# axiom_beta_sensor_cmv12000_tht_v0_16_r1_.net
KiCad netlist of a schematic drawn in EAGLE
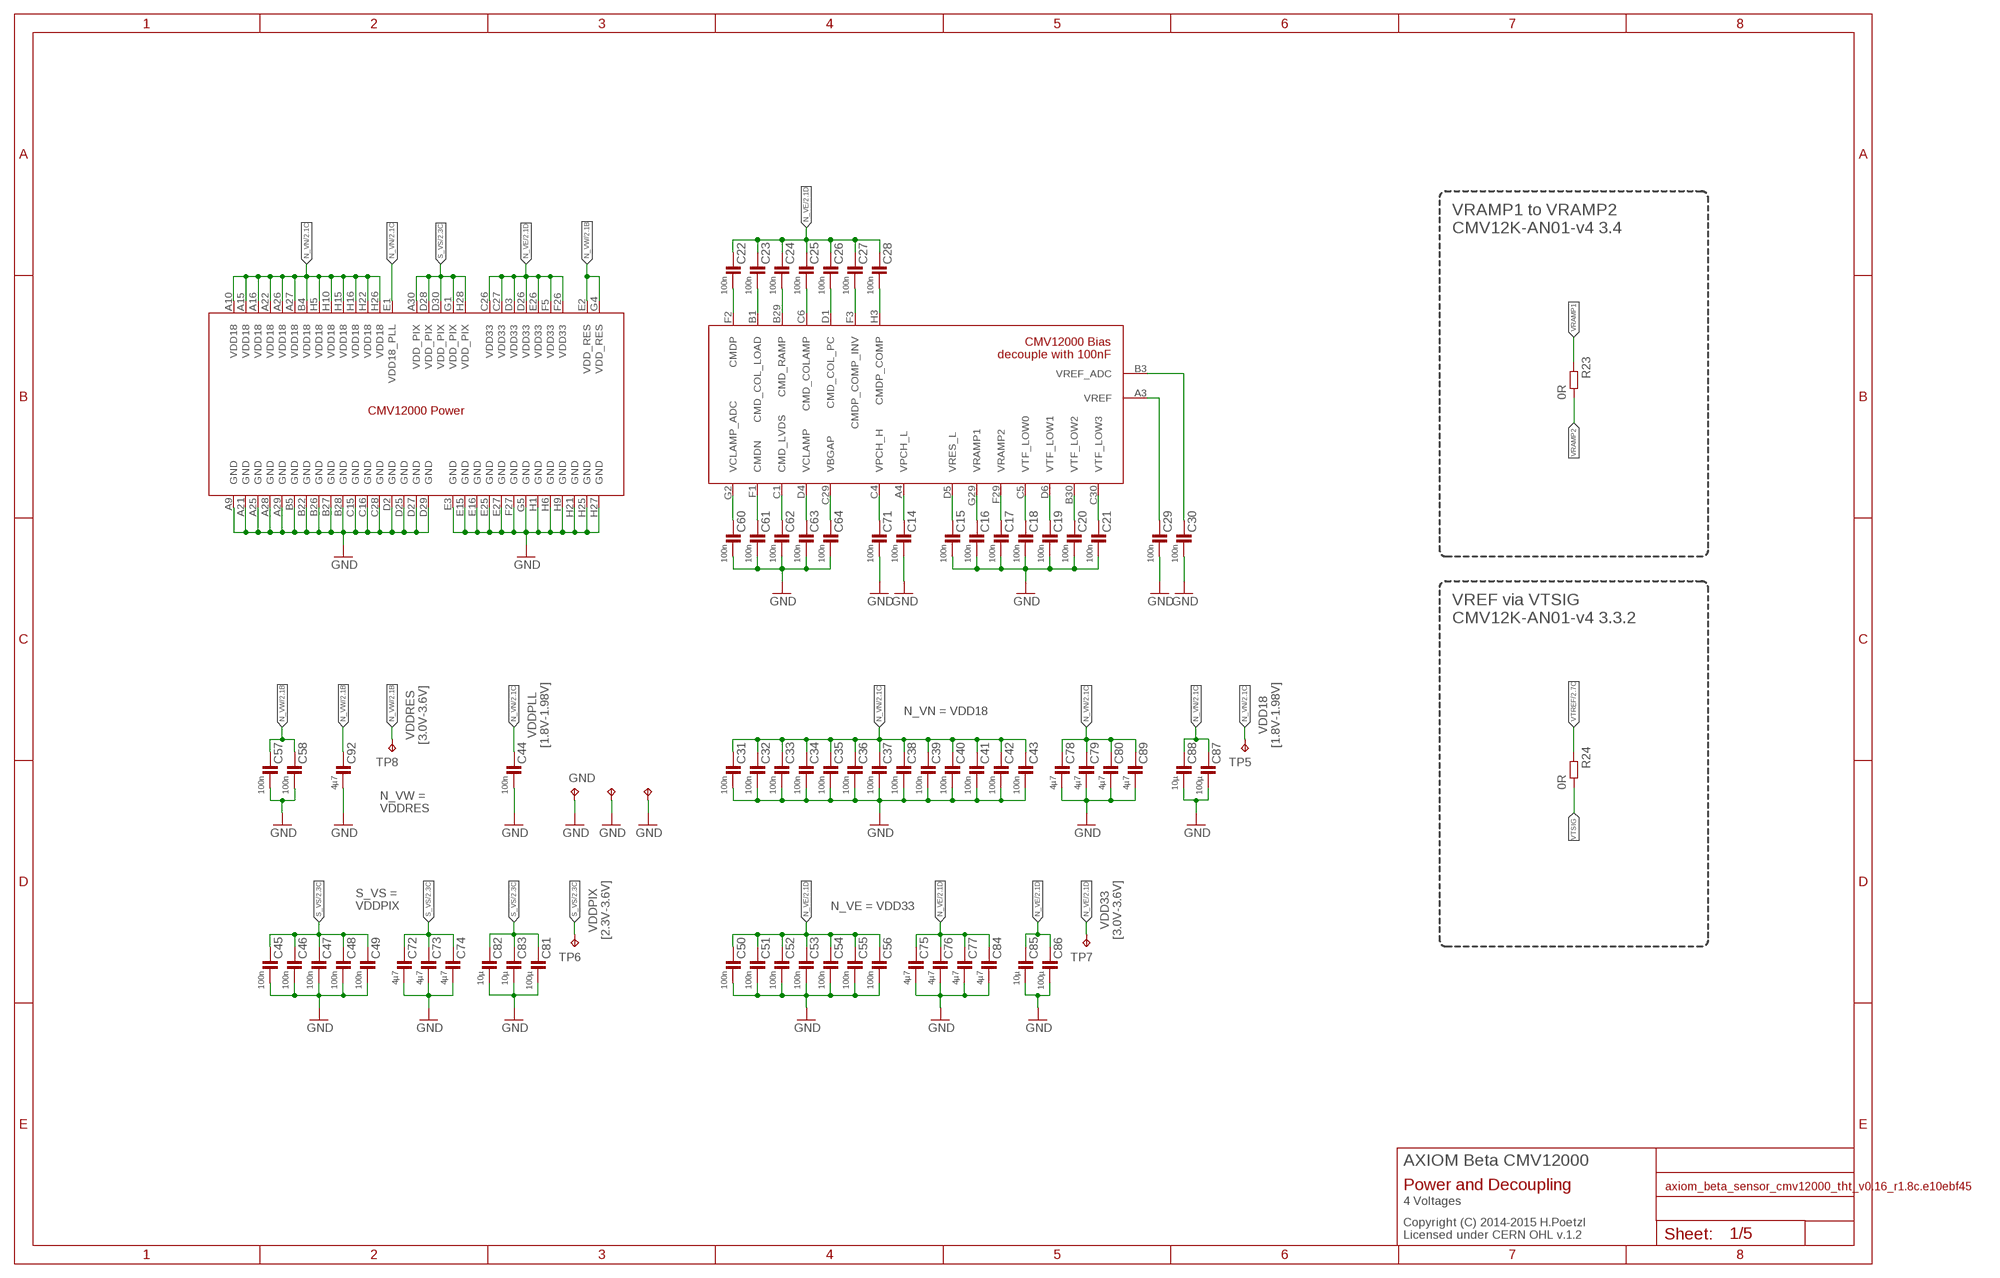
[diagram p0: schematic, sheet 1]
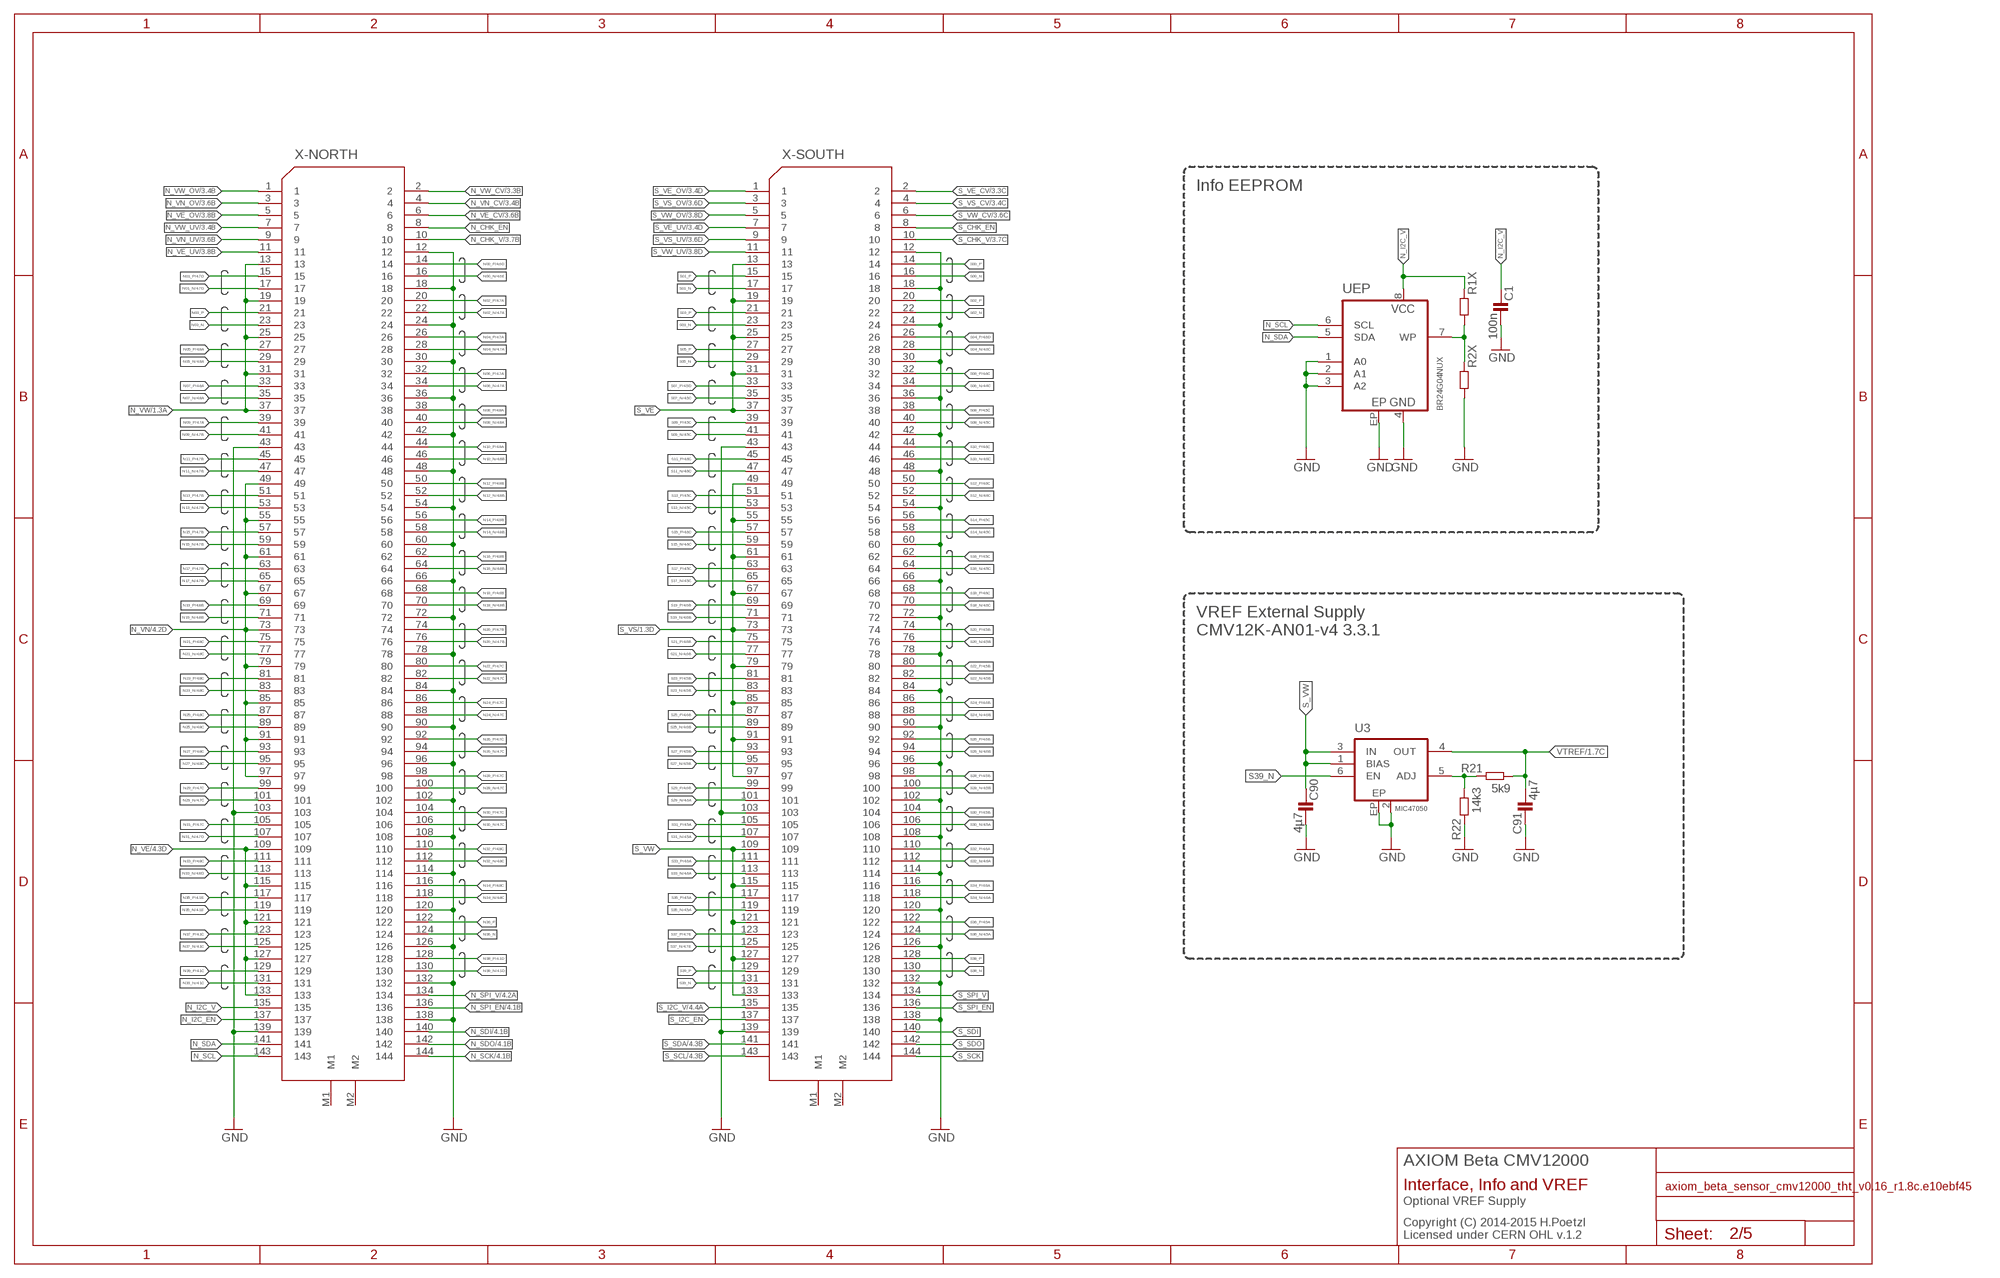
[diagram p1: schematic, sheet 2]
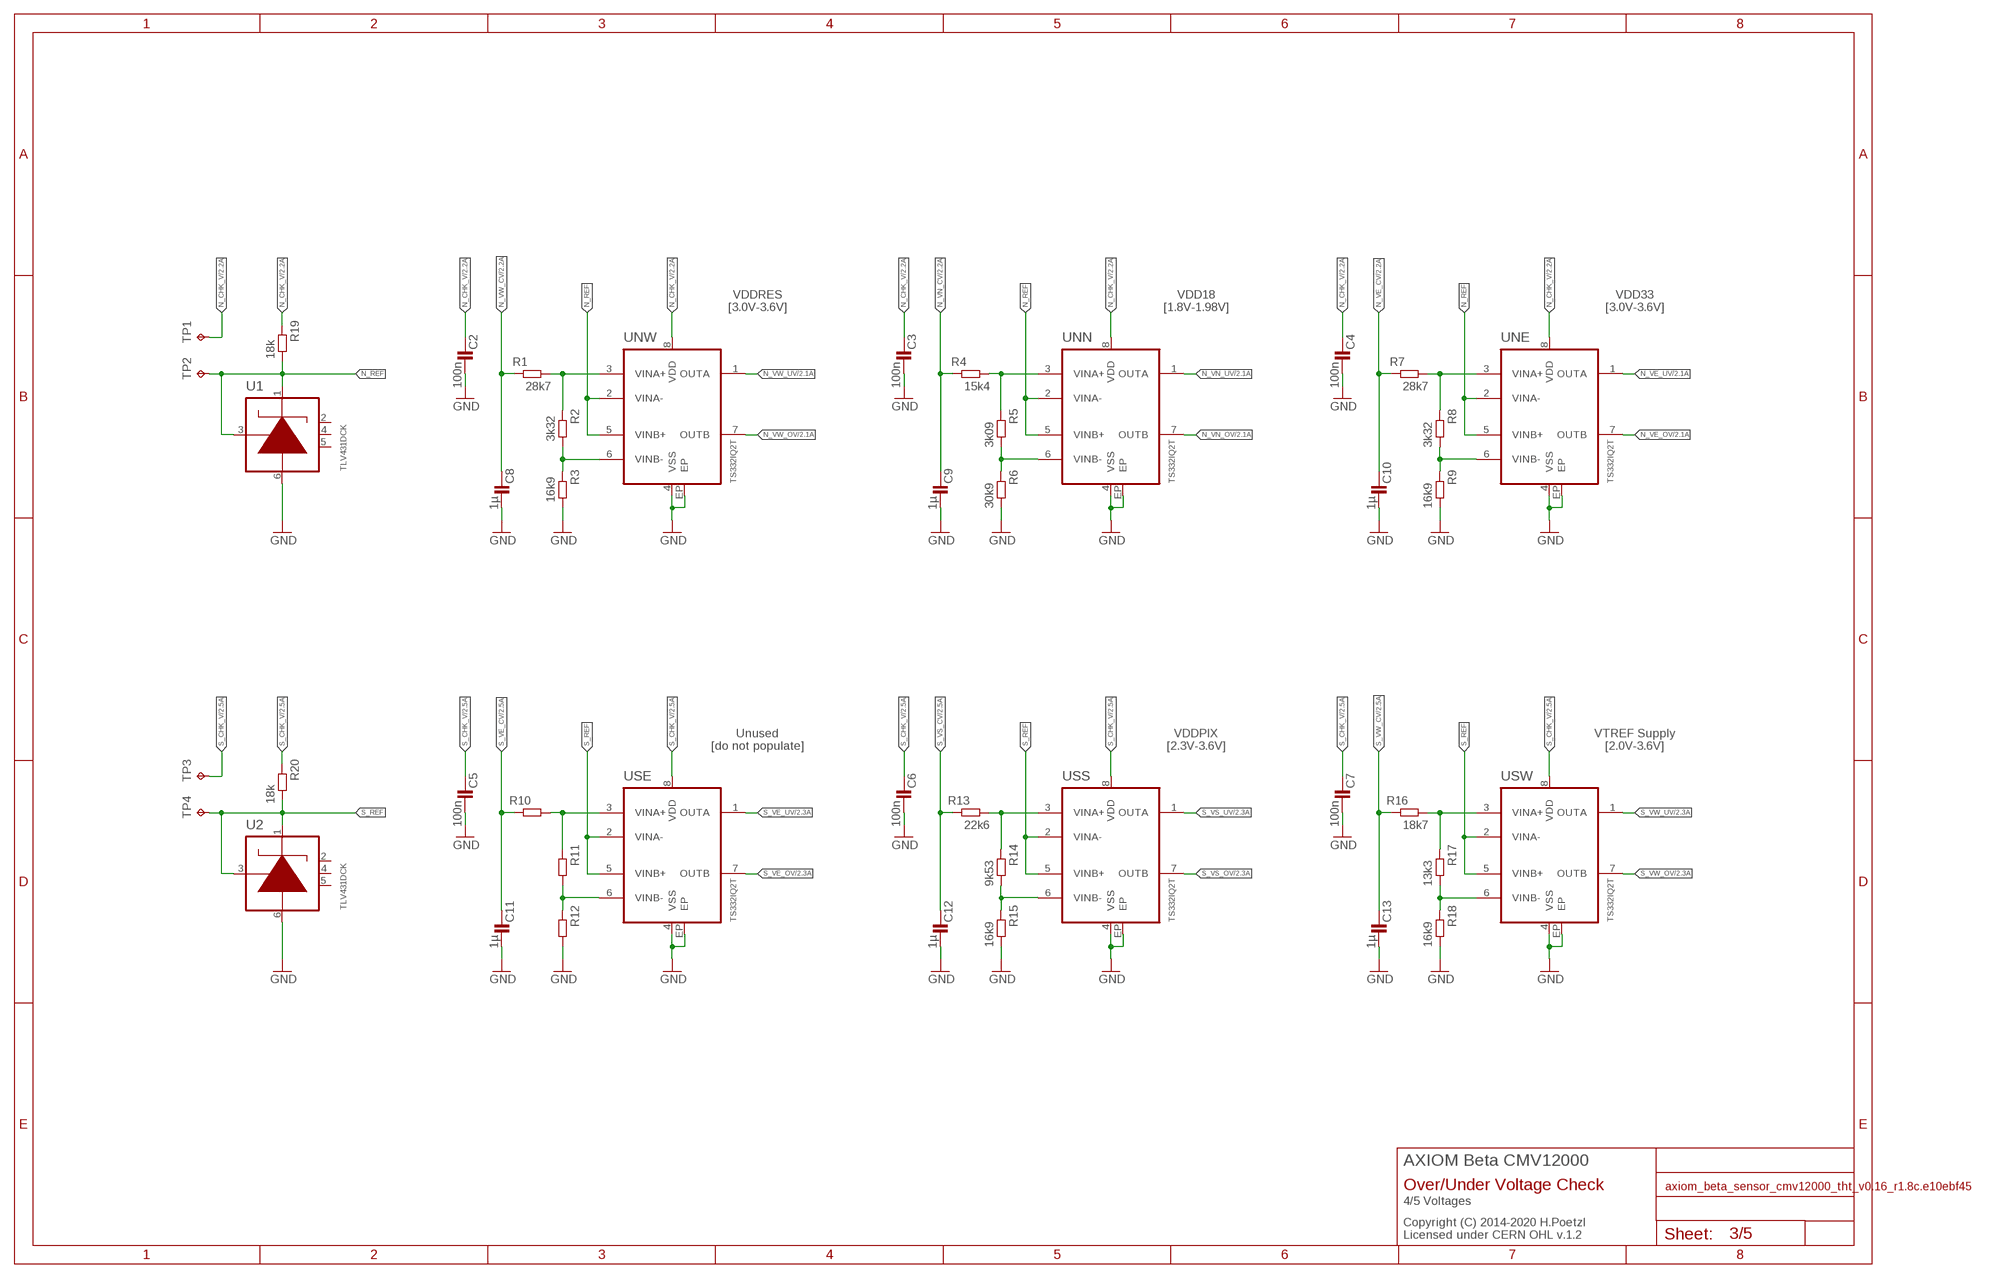
[diagram p2: schematic, sheet 3]
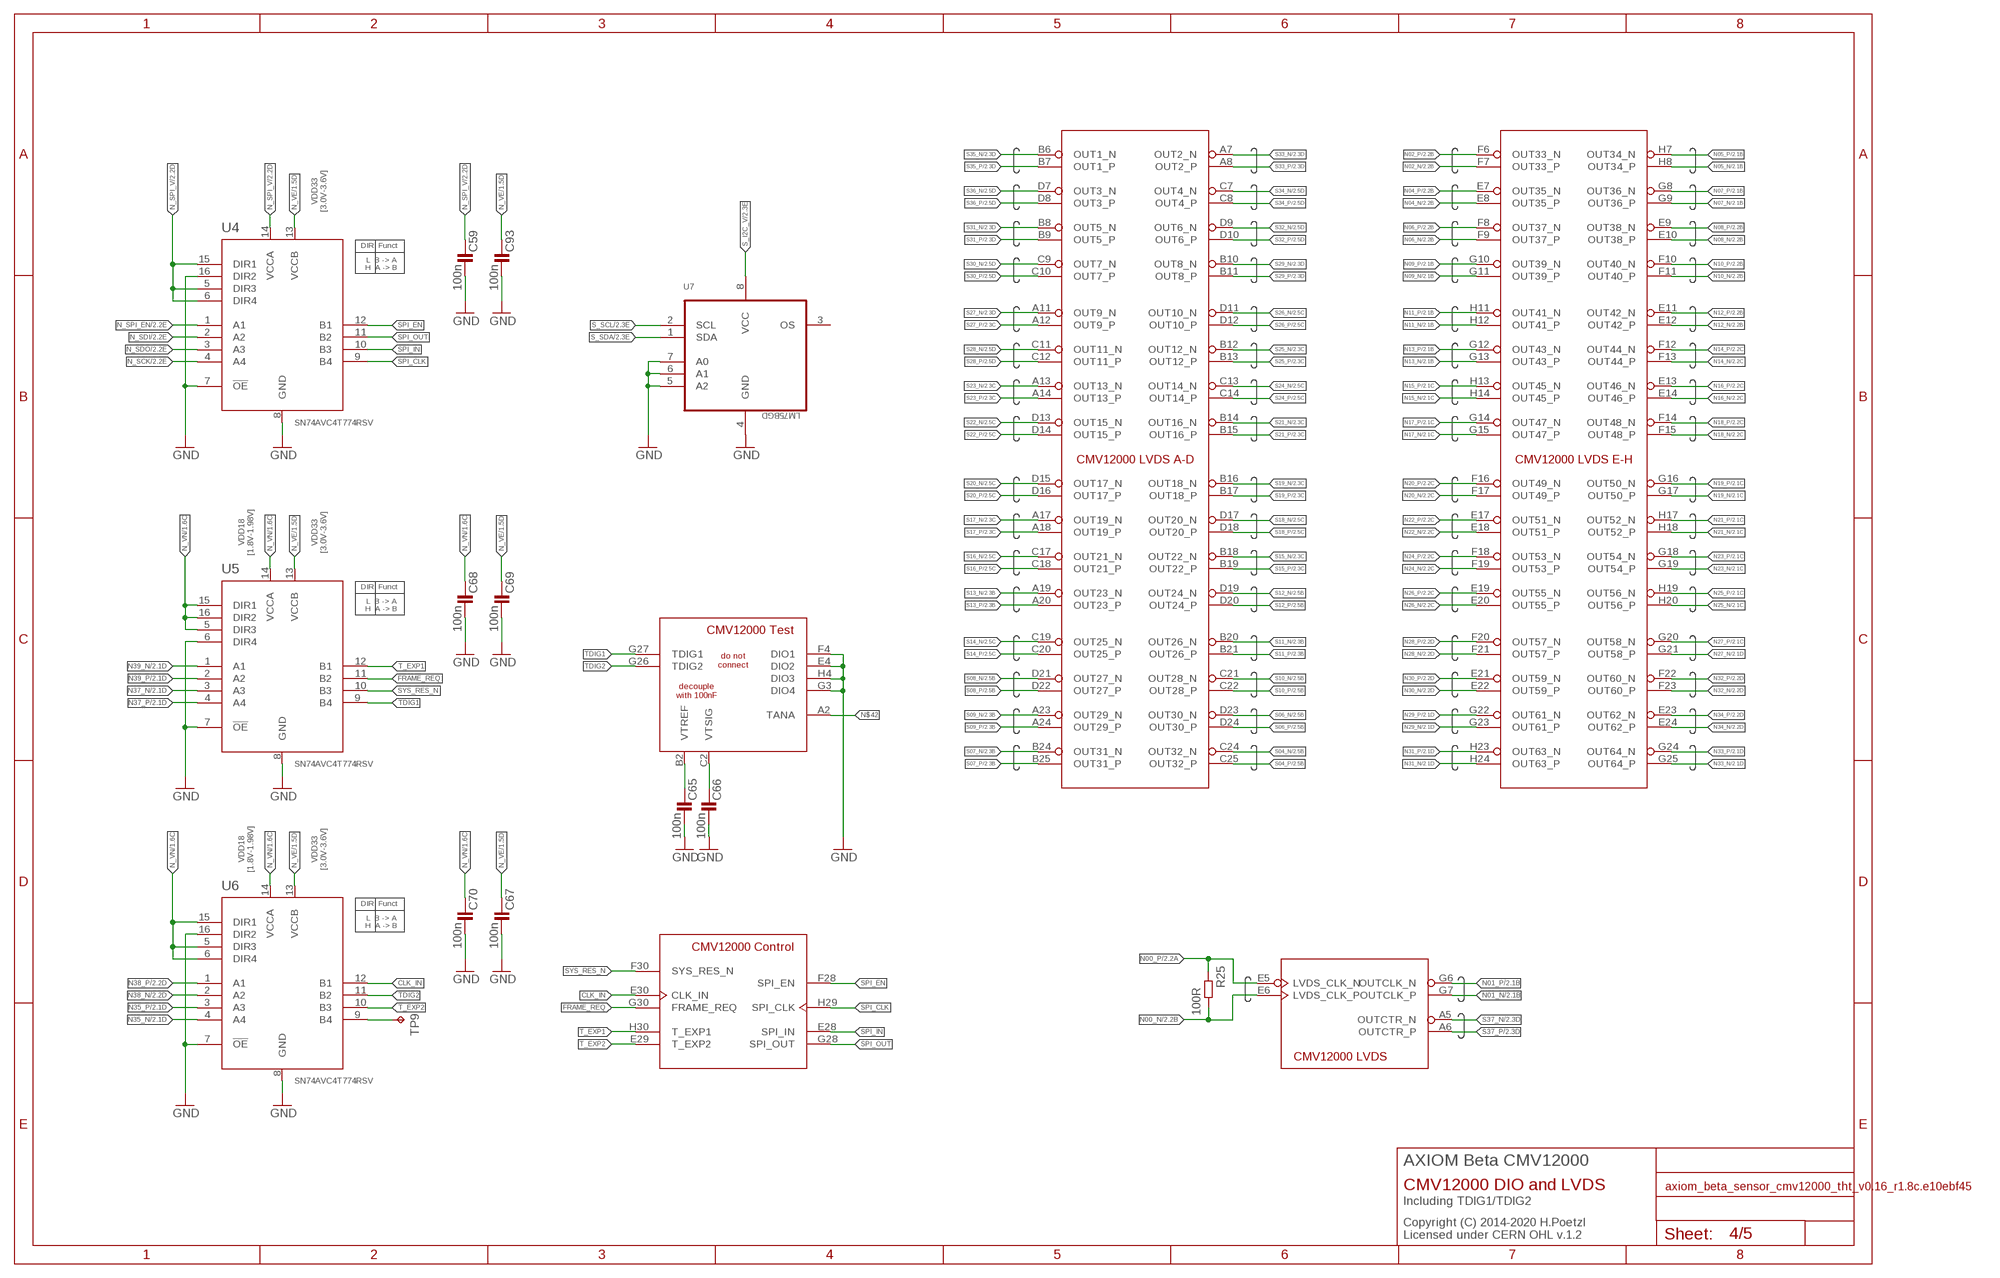
[diagram p3: schematic, sheet 4]
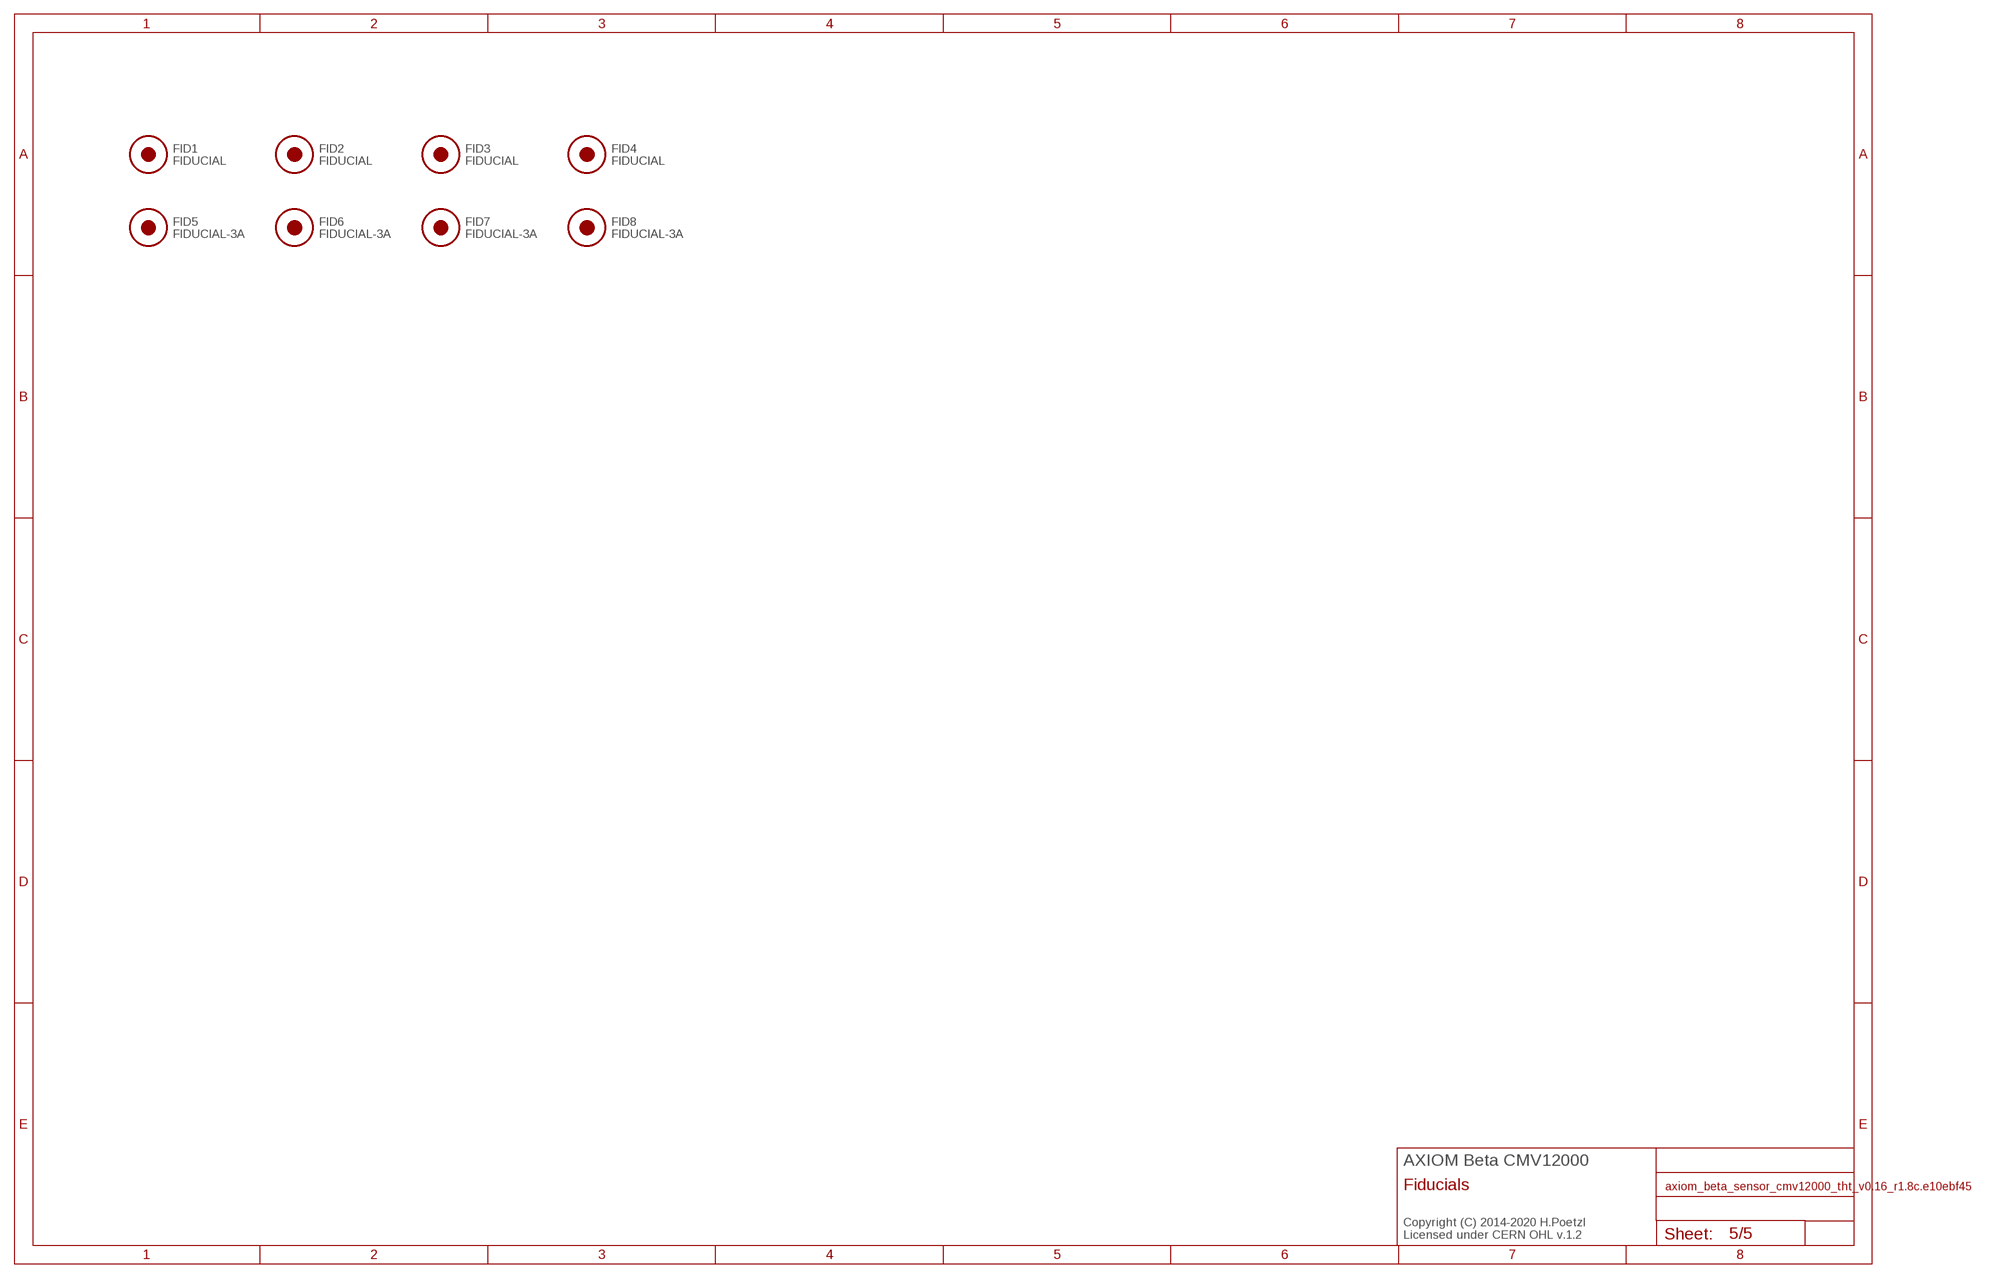
[diagram p4: schematic, sheet 5]

(export (version "E")
  (design (tool "Eeschema 10.0.6"))
  (components
    (comp (ref "C1")
      (value "100n")
      (footprint "eagle-import:0402-C")
      (libsource (lib "eagle-import") (part "C0402-C"))
    )
    (comp (ref "C90")
      (value "4µ7")
      (footprint "eagle-import:0402-C")
      (libsource (lib "eagle-import") (part "C0402-C"))
    )
    (comp (ref "C91")
      (value "4µ7")
      (footprint "eagle-import:0402-C")
      (libsource (lib "eagle-import") (part "C0402-C"))
    )
    (comp (ref "R1X")
      (value "R0402-C")
      (footprint "eagle-import:0402-C")
      (libsource (lib "eagle-import") (part "R0402-C"))
    )
    (comp (ref "R2X")
      (value "R0402-C")
      (footprint "eagle-import:0402-C")
      (libsource (lib "eagle-import") (part "R0402-C"))
    )
    (comp (ref "R21")
      (value "5k9")
      (footprint "eagle-import:0402-C")
      (libsource (lib "eagle-import") (part "R0402-C"))
    )
    (comp (ref "R22")
      (value "14k3")
      (footprint "eagle-import:0402-C")
      (libsource (lib "eagle-import") (part "R0402-C"))
    )
    (comp (ref "U3")
      (value "MIC47050")
      (footprint "eagle-import:MLF-6")
      (libsource (lib "eagle-import") (part "MIC47050-ADJ"))
    )
    (comp (ref "UEP")
      (value "BR24G04NUX")
      (footprint "eagle-import:DFN200X300X100-9N")
      (libsource (lib "eagle-import") (part "BR24G04NUX"))
    )
    (comp (ref "X-NORTH")
      (value "FX10-144P")
      (footprint "eagle-import:FX10A-144P")
      (libsource (lib "eagle-import") (part "FX10-144P"))
    )
    (comp (ref "X-SOUTH")
      (value "FX10-144P")
      (footprint "eagle-import:FX10A-144P")
      (libsource (lib "eagle-import") (part "FX10-144P"))
    )
    (comp (ref "C14")
      (value "100n")
      (footprint "eagle-import:0402-C")
      (libsource (lib "eagle-import") (part "C0402-C"))
    )
    (comp (ref "C15")
      (value "100n")
      (footprint "eagle-import:0402-C")
      (libsource (lib "eagle-import") (part "C0402-C"))
    )
    (comp (ref "C16")
      (value "100n")
      (footprint "eagle-import:0402-C")
      (libsource (lib "eagle-import") (part "C0402-C"))
    )
    (comp (ref "C17")
      (value "100n")
      (footprint "eagle-import:0402-C")
      (libsource (lib "eagle-import") (part "C0402-C"))
    )
    (comp (ref "C18")
      (value "100n")
      (footprint "eagle-import:0402-C")
      (libsource (lib "eagle-import") (part "C0402-C"))
    )
    (comp (ref "C19")
      (value "100n")
      (footprint "eagle-import:0402-C")
      (libsource (lib "eagle-import") (part "C0402-C"))
    )
    (comp (ref "C20")
      (value "100n")
      (footprint "eagle-import:0402-C")
      (libsource (lib "eagle-import") (part "C0402-C"))
    )
    (comp (ref "C21")
      (value "100n")
      (footprint "eagle-import:0402-C")
      (libsource (lib "eagle-import") (part "C0402-C"))
    )
    (comp (ref "C22")
      (value "100n")
      (footprint "eagle-import:0402-C")
      (libsource (lib "eagle-import") (part "C0402-C"))
    )
    (comp (ref "C23")
      (value "100n")
      (footprint "eagle-import:0402-C")
      (libsource (lib "eagle-import") (part "C0402-C"))
    )
    (comp (ref "C24")
      (value "100n")
      (footprint "eagle-import:0402-C")
      (libsource (lib "eagle-import") (part "C0402-C"))
    )
    (comp (ref "C25")
      (value "100n")
      (footprint "eagle-import:0402-C")
      (libsource (lib "eagle-import") (part "C0402-C"))
    )
    (comp (ref "C26")
      (value "100n")
      (footprint "eagle-import:0402-C")
      (libsource (lib "eagle-import") (part "C0402-C"))
    )
    (comp (ref "C27")
      (value "100n")
      (footprint "eagle-import:0402-C")
      (libsource (lib "eagle-import") (part "C0402-C"))
    )
    (comp (ref "C28")
      (value "100n")
      (footprint "eagle-import:0402-C")
      (libsource (lib "eagle-import") (part "C0402-C"))
    )
    (comp (ref "C29")
      (value "100n")
      (footprint "eagle-import:0402-C")
      (libsource (lib "eagle-import") (part "C0402-C"))
    )
    (comp (ref "C30")
      (value "100n")
      (footprint "eagle-import:0402-C")
      (libsource (lib "eagle-import") (part "C0402-C"))
    )
    (comp (ref "C31")
      (value "100n")
      (footprint "eagle-import:0402-C")
      (libsource (lib "eagle-import") (part "C0402-C"))
    )
    (comp (ref "C32")
      (value "100n")
      (footprint "eagle-import:0402-C")
      (libsource (lib "eagle-import") (part "C0402-C"))
    )
    (comp (ref "C33")
      (value "100n")
      (footprint "eagle-import:0402-C")
      (libsource (lib "eagle-import") (part "C0402-C"))
    )
    (comp (ref "C34")
      (value "100n")
      (footprint "eagle-import:0402-C")
      (libsource (lib "eagle-import") (part "C0402-C"))
    )
    (comp (ref "C35")
      (value "100n")
      (footprint "eagle-import:0402-C")
      (libsource (lib "eagle-import") (part "C0402-C"))
    )
    (comp (ref "C36")
      (value "100n")
      (footprint "eagle-import:0402-C")
      (libsource (lib "eagle-import") (part "C0402-C"))
    )
    (comp (ref "C37")
      (value "100n")
      (footprint "eagle-import:0402-C")
      (libsource (lib "eagle-import") (part "C0402-C"))
    )
    (comp (ref "C38")
      (value "100n")
      (footprint "eagle-import:0402-C")
      (libsource (lib "eagle-import") (part "C0402-C"))
    )
    (comp (ref "C39")
      (value "100n")
      (footprint "eagle-import:0402-C")
      (libsource (lib "eagle-import") (part "C0402-C"))
    )
    (comp (ref "C40")
      (value "100n")
      (footprint "eagle-import:0402-C")
      (libsource (lib "eagle-import") (part "C0402-C"))
    )
    (comp (ref "C41")
      (value "100n")
      (footprint "eagle-import:0402-C")
      (libsource (lib "eagle-import") (part "C0402-C"))
    )
    (comp (ref "C42")
      (value "100n")
      (footprint "eagle-import:0402-C")
      (libsource (lib "eagle-import") (part "C0402-C"))
    )
    (comp (ref "C43")
      (value "100n")
      (footprint "eagle-import:0402-C")
      (libsource (lib "eagle-import") (part "C0402-C"))
    )
    (comp (ref "C44")
      (value "100n")
      (footprint "eagle-import:0402-C")
      (libsource (lib "eagle-import") (part "C0402-C"))
    )
    (comp (ref "C45")
      (value "100n")
      (footprint "eagle-import:0402-C")
      (libsource (lib "eagle-import") (part "C0402-C"))
    )
    (comp (ref "C46")
      (value "100n")
      (footprint "eagle-import:0402-C")
      (libsource (lib "eagle-import") (part "C0402-C"))
    )
    (comp (ref "C47")
      (value "100n")
      (footprint "eagle-import:0402-C")
      (libsource (lib "eagle-import") (part "C0402-C"))
    )
    (comp (ref "C48")
      (value "100n")
      (footprint "eagle-import:0402-C")
      (libsource (lib "eagle-import") (part "C0402-C"))
    )
    (comp (ref "C49")
      (value "100n")
      (footprint "eagle-import:0402-C")
      (libsource (lib "eagle-import") (part "C0402-C"))
    )
    (comp (ref "C50")
      (value "100n")
      (footprint "eagle-import:0402-C")
      (libsource (lib "eagle-import") (part "C0402-C"))
    )
    (comp (ref "C51")
      (value "100n")
      (footprint "eagle-import:0402-C")
      (libsource (lib "eagle-import") (part "C0402-C"))
    )
    (comp (ref "C52")
      (value "100n")
      (footprint "eagle-import:0402-C")
      (libsource (lib "eagle-import") (part "C0402-C"))
    )
    (comp (ref "C53")
      (value "100n")
      (footprint "eagle-import:0402-C")
      (libsource (lib "eagle-import") (part "C0402-C"))
    )
    (comp (ref "C54")
      (value "100n")
      (footprint "eagle-import:0402-C")
      (libsource (lib "eagle-import") (part "C0402-C"))
    )
    (comp (ref "C55")
      (value "100n")
      (footprint "eagle-import:0402-C")
      (libsource (lib "eagle-import") (part "C0402-C"))
    )
    (comp (ref "C56")
      (value "100n")
      (footprint "eagle-import:0402-C")
      (libsource (lib "eagle-import") (part "C0402-C"))
    )
    (comp (ref "C57")
      (value "100n")
      (footprint "eagle-import:0402-C")
      (libsource (lib "eagle-import") (part "C0402-C"))
    )
    (comp (ref "C58")
      (value "100n")
      (footprint "eagle-import:0402-C")
      (libsource (lib "eagle-import") (part "C0402-C"))
    )
    (comp (ref "C60")
      (value "100n")
      (footprint "eagle-import:0402-C")
      (libsource (lib "eagle-import") (part "C0402-C"))
    )
    (comp (ref "C61")
      (value "100n")
      (footprint "eagle-import:0402-C")
      (libsource (lib "eagle-import") (part "C0402-C"))
    )
    (comp (ref "C62")
      (value "100n")
      (footprint "eagle-import:0402-C")
      (libsource (lib "eagle-import") (part "C0402-C"))
    )
    (comp (ref "C63")
      (value "100n")
      (footprint "eagle-import:0402-C")
      (libsource (lib "eagle-import") (part "C0402-C"))
    )
    (comp (ref "C64")
      (value "100n")
      (footprint "eagle-import:0402-C")
      (libsource (lib "eagle-import") (part "C0402-C"))
    )
    (comp (ref "C71")
      (value "100n")
      (footprint "eagle-import:0402-C")
      (libsource (lib "eagle-import") (part "C0402-C"))
    )
    (comp (ref "C72")
      (value "4µ7")
      (footprint "eagle-import:0402-B")
      (libsource (lib "eagle-import") (part "C0402-B"))
    )
    (comp (ref "C73")
      (value "4µ7")
      (footprint "eagle-import:0402-C")
      (libsource (lib "eagle-import") (part "C0402-C"))
    )
    (comp (ref "C74")
      (value "4µ7")
      (footprint "eagle-import:0402-C")
      (libsource (lib "eagle-import") (part "C0402-C"))
    )
    (comp (ref "C75")
      (value "4µ7")
      (footprint "eagle-import:0402-C")
      (libsource (lib "eagle-import") (part "C0402-C"))
    )
    (comp (ref "C76")
      (value "4µ7")
      (footprint "eagle-import:0402-C")
      (libsource (lib "eagle-import") (part "C0402-C"))
    )
    (comp (ref "C77")
      (value "4µ7")
      (footprint "eagle-import:0402-B")
      (libsource (lib "eagle-import") (part "C0402-B"))
    )
    (comp (ref "C78")
      (value "4µ7")
      (footprint "eagle-import:0402-B")
      (libsource (lib "eagle-import") (part "C0402-B"))
    )
    (comp (ref "C79")
      (value "4µ7")
      (footprint "eagle-import:0402-C")
      (libsource (lib "eagle-import") (part "C0402-C"))
    )
    (comp (ref "C80")
      (value "4µ7")
      (footprint "eagle-import:0402-C")
      (libsource (lib "eagle-import") (part "C0402-C"))
    )
    (comp (ref "C81")
      (value "100µ")
      (footprint "eagle-import:1206-B")
      (libsource (lib "eagle-import") (part "C1206-B"))
    )
    (comp (ref "C82")
      (value "10µ")
      (footprint "eagle-import:0603-C")
      (libsource (lib "eagle-import") (part "C0603-C"))
    )
    (comp (ref "C83")
      (value "10µ")
      (footprint "eagle-import:0603-C")
      (libsource (lib "eagle-import") (part "C0603-C"))
    )
    (comp (ref "C84")
      (value "4µ7")
      (footprint "eagle-import:0402-C")
      (libsource (lib "eagle-import") (part "C0402-C"))
    )
    (comp (ref "C85")
      (value "10µ")
      (footprint "eagle-import:0603-C")
      (libsource (lib "eagle-import") (part "C0603-C"))
    )
    (comp (ref "C86")
      (value "100µ")
      (footprint "eagle-import:1206-B")
      (libsource (lib "eagle-import") (part "C1206-B"))
    )
    (comp (ref "C87")
      (value "100µ")
      (footprint "eagle-import:1206-B")
      (libsource (lib "eagle-import") (part "C1206-B"))
    )
    (comp (ref "C88")
      (value "10µ")
      (footprint "eagle-import:0603-C")
      (libsource (lib "eagle-import") (part "C0603-C"))
    )
    (comp (ref "C89")
      (value "4µ7")
      (footprint "eagle-import:0402-C")
      (libsource (lib "eagle-import") (part "C0402-C"))
    )
    (comp (ref "C92")
      (value "4µ7")
      (footprint "eagle-import:0402-C")
      (libsource (lib "eagle-import") (part "C0402-C"))
    )
    (comp (ref "GND")
      (value "TPTP10R")
      (footprint "eagle-import:TP10R")
      (libsource (lib "eagle-import") (part "TPTP10R"))
    )
    (comp (ref "GND75")
      (value "TPTP10R")
      (footprint "eagle-import:TP10R")
      (libsource (lib "eagle-import") (part "TPTP10R"))
    )
    (comp (ref "GND77")
      (value "TPTP10R")
      (footprint "eagle-import:TP10R")
      (libsource (lib "eagle-import") (part "TPTP10R"))
    )
    (comp (ref "R23")
      (value "0R")
      (footprint "eagle-import:0402-C")
      (libsource (lib "eagle-import") (part "R0402-C"))
    )
    (comp (ref "R24")
      (value "0R")
      (footprint "eagle-import:0402-C")
      (libsource (lib "eagle-import") (part "R0402-C"))
    )
    (comp (ref "SENSOR")
      (value "CMV12000ANDON")
      (footprint "eagle-import:10-30-07-237-400T4")
      (libsource (lib "eagle-import") (part "CMV12000ANDON"))
    )
    (comp (ref "TP5")
      (value "TPTP10R")
      (footprint "eagle-import:TP10R")
      (libsource (lib "eagle-import") (part "TPTP10R"))
    )
    (comp (ref "TP6")
      (value "TPTP10R")
      (footprint "eagle-import:TP10R")
      (libsource (lib "eagle-import") (part "TPTP10R"))
    )
    (comp (ref "TP7")
      (value "TPTP10R")
      (footprint "eagle-import:TP10R")
      (libsource (lib "eagle-import") (part "TPTP10R"))
    )
    (comp (ref "TP8")
      (value "TPTP10R")
      (footprint "eagle-import:TP10R")
      (libsource (lib "eagle-import") (part "TPTP10R"))
    )
    (comp (ref "FID1")
      (value "FIDUCIAL")
      (footprint "eagle-import:FID_ARROW")
      (libsource (lib "eagle-import") (part "FIDUCIAL"))
    )
    (comp (ref "FID2")
      (value "FIDUCIAL")
      (footprint "eagle-import:FID_ARROW")
      (libsource (lib "eagle-import") (part "FIDUCIAL"))
    )
    (comp (ref "FID3")
      (value "FIDUCIAL")
      (footprint "eagle-import:FID_ARROW")
      (libsource (lib "eagle-import") (part "FIDUCIAL"))
    )
    (comp (ref "FID4")
      (value "FIDUCIAL")
      (footprint "eagle-import:FID_ARROW")
      (libsource (lib "eagle-import") (part "FIDUCIAL"))
    )
    (comp (ref "FID5")
      (value "FIDUCIAL-3A")
      (footprint "eagle-import:FID_3ARROW")
      (libsource (lib "eagle-import") (part "FIDUCIAL-3A"))
    )
    (comp (ref "FID6")
      (value "FIDUCIAL-3A")
      (footprint "eagle-import:FID_3ARROW")
      (libsource (lib "eagle-import") (part "FIDUCIAL-3A"))
    )
    (comp (ref "FID7")
      (value "FIDUCIAL-3A")
      (footprint "eagle-import:FID_3ARROW")
      (libsource (lib "eagle-import") (part "FIDUCIAL-3A"))
    )
    (comp (ref "FID8")
      (value "FIDUCIAL-3A")
      (footprint "eagle-import:FID_3ARROW")
      (libsource (lib "eagle-import") (part "FIDUCIAL-3A"))
    )
    (comp (ref "C59")
      (value "100n")
      (footprint "eagle-import:0402-C")
      (libsource (lib "eagle-import") (part "C0402-C"))
    )
    (comp (ref "C65")
      (value "100n")
      (footprint "eagle-import:0402-C")
      (libsource (lib "eagle-import") (part "C0402-C"))
    )
    (comp (ref "C66")
      (value "100n")
      (footprint "eagle-import:0402-C")
      (libsource (lib "eagle-import") (part "C0402-C"))
    )
    (comp (ref "C67")
      (value "100n")
      (footprint "eagle-import:0402-C")
      (libsource (lib "eagle-import") (part "C0402-C"))
    )
    (comp (ref "C68")
      (value "100n")
      (footprint "eagle-import:0402-C")
      (libsource (lib "eagle-import") (part "C0402-C"))
    )
    (comp (ref "C69")
      (value "100n")
      (footprint "eagle-import:0402-C")
      (libsource (lib "eagle-import") (part "C0402-C"))
    )
    (comp (ref "C70")
      (value "100n")
      (footprint "eagle-import:0402-C")
      (libsource (lib "eagle-import") (part "C0402-C"))
    )
    (comp (ref "C93")
      (value "100n")
      (footprint "eagle-import:0402-C")
      (libsource (lib "eagle-import") (part "C0402-C"))
    )
    (comp (ref "R25")
      (value "100R")
      (footprint "eagle-import:0402-C")
      (libsource (lib "eagle-import") (part "R0402-C"))
    )
    (comp (ref "TP9")
      (value "TPTP10R")
      (footprint "eagle-import:TP10R")
      (libsource (lib "eagle-import") (part "TPTP10R"))
    )
    (comp (ref "U4")
      (value "SN74AVC4T774RSV")
      (footprint "eagle-import:QFN40P185X265X55-16N")
      (libsource (lib "eagle-import") (part "SN74AVC4T774RSV"))
    )
    (comp (ref "U5")
      (value "SN74AVC4T774RSV")
      (footprint "eagle-import:QFN40P185X265X55-16N")
      (libsource (lib "eagle-import") (part "SN74AVC4T774RSV"))
    )
    (comp (ref "U6")
      (value "SN74AVC4T774RSV")
      (footprint "eagle-import:QFN40P185X265X55-16N")
      (libsource (lib "eagle-import") (part "SN74AVC4T774RSV"))
    )
    (comp (ref "U7")
      (value "LM75BGD")
      (footprint "eagle-import:SOT996-2_3")
      (libsource (lib "eagle-import") (part "LM75BGD"))
    )
    (comp (ref "C2")
      (value "100n")
      (footprint "eagle-import:0402-C")
      (libsource (lib "eagle-import") (part "C0402-C"))
    )
    (comp (ref "C3")
      (value "100n")
      (footprint "eagle-import:0402-C")
      (libsource (lib "eagle-import") (part "C0402-C"))
    )
    (comp (ref "C4")
      (value "100n")
      (footprint "eagle-import:0402-C")
      (libsource (lib "eagle-import") (part "C0402-C"))
    )
    (comp (ref "C5")
      (value "100n")
      (footprint "eagle-import:0402-C")
      (libsource (lib "eagle-import") (part "C0402-C"))
    )
    (comp (ref "C6")
      (value "100n")
      (footprint "eagle-import:0402-C")
      (libsource (lib "eagle-import") (part "C0402-C"))
    )
    (comp (ref "C7")
      (value "100n")
      (footprint "eagle-import:0402-C")
      (libsource (lib "eagle-import") (part "C0402-C"))
    )
    (comp (ref "C8")
      (value "1µ")
      (footprint "eagle-import:0402-C")
      (libsource (lib "eagle-import") (part "C0402-C"))
    )
    (comp (ref "C9")
      (value "1µ")
      (footprint "eagle-import:0402-C")
      (libsource (lib "eagle-import") (part "C0402-C"))
    )
    (comp (ref "C10")
      (value "1µ")
      (footprint "eagle-import:0402-C")
      (libsource (lib "eagle-import") (part "C0402-C"))
    )
    (comp (ref "C11")
      (value "1µ")
      (footprint "eagle-import:0402-C")
      (libsource (lib "eagle-import") (part "C0402-C"))
    )
    (comp (ref "C12")
      (value "1µ")
      (footprint "eagle-import:0402-C")
      (libsource (lib "eagle-import") (part "C0402-C"))
    )
    (comp (ref "C13")
      (value "1µ")
      (footprint "eagle-import:0402-C")
      (libsource (lib "eagle-import") (part "C0402-C"))
    )
    (comp (ref "R1")
      (value "28k7")
      (footprint "eagle-import:0402-C")
      (libsource (lib "eagle-import") (part "R0402-C"))
    )
    (comp (ref "R2")
      (value "3k32")
      (footprint "eagle-import:0402-C")
      (libsource (lib "eagle-import") (part "R0402-C"))
    )
    (comp (ref "R3")
      (value "16k9")
      (footprint "eagle-import:0402-C")
      (libsource (lib "eagle-import") (part "R0402-C"))
    )
    (comp (ref "R4")
      (value "15k4")
      (footprint "eagle-import:0402-C")
      (libsource (lib "eagle-import") (part "R0402-C"))
    )
    (comp (ref "R5")
      (value "3k09")
      (footprint "eagle-import:0402-C")
      (libsource (lib "eagle-import") (part "R0402-C"))
    )
    (comp (ref "R6")
      (value "30k9")
      (footprint "eagle-import:0402-C")
      (libsource (lib "eagle-import") (part "R0402-C"))
    )
    (comp (ref "R7")
      (value "28k7")
      (footprint "eagle-import:0402-C")
      (libsource (lib "eagle-import") (part "R0402-C"))
    )
    (comp (ref "R8")
      (value "3k32")
      (footprint "eagle-import:0402-C")
      (libsource (lib "eagle-import") (part "R0402-C"))
    )
    (comp (ref "R9")
      (value "16k9")
      (footprint "eagle-import:0402-C")
      (libsource (lib "eagle-import") (part "R0402-C"))
    )
    (comp (ref "R10")
      (value "R0402-C")
      (footprint "eagle-import:0402-C")
      (libsource (lib "eagle-import") (part "R0402-C"))
    )
    (comp (ref "R11")
      (value "R0402-C")
      (footprint "eagle-import:0402-C")
      (libsource (lib "eagle-import") (part "R0402-C"))
    )
    (comp (ref "R12")
      (value "R0402-C")
      (footprint "eagle-import:0402-C")
      (libsource (lib "eagle-import") (part "R0402-C"))
    )
    (comp (ref "R13")
      (value "22k6")
      (footprint "eagle-import:0402-C")
      (libsource (lib "eagle-import") (part "R0402-C"))
    )
    (comp (ref "R14")
      (value "9k53")
      (footprint "eagle-import:0402-C")
      (libsource (lib "eagle-import") (part "R0402-C"))
    )
    (comp (ref "R15")
      (value "16k9")
      (footprint "eagle-import:0402-C")
      (libsource (lib "eagle-import") (part "R0402-C"))
    )
    (comp (ref "R16")
      (value "18k7")
      (footprint "eagle-import:0402-C")
      (libsource (lib "eagle-import") (part "R0402-C"))
    )
    (comp (ref "R17")
      (value "13k3")
      (footprint "eagle-import:0402-C")
      (libsource (lib "eagle-import") (part "R0402-C"))
    )
    (comp (ref "R18")
      (value "16k9")
      (footprint "eagle-import:0402-C")
      (libsource (lib "eagle-import") (part "R0402-C"))
    )
    (comp (ref "R19")
      (value "18k")
      (footprint "eagle-import:0402-C")
      (libsource (lib "eagle-import") (part "R0402-C"))
    )
    (comp (ref "R20")
      (value "18k")
      (footprint "eagle-import:0402-C")
      (libsource (lib "eagle-import") (part "R0402-C"))
    )
    (comp (ref "TP1")
      (value "TPTP10R")
      (footprint "eagle-import:TP10R")
      (libsource (lib "eagle-import") (part "TPTP10R"))
    )
    (comp (ref "TP2")
      (value "TPTP10R")
      (footprint "eagle-import:TP10R")
      (libsource (lib "eagle-import") (part "TPTP10R"))
    )
    (comp (ref "TP3")
      (value "TPTP10R")
      (footprint "eagle-import:TP10R")
      (libsource (lib "eagle-import") (part "TPTP10R"))
    )
    (comp (ref "TP4")
      (value "TPTP10R")
      (footprint "eagle-import:TP10R")
      (libsource (lib "eagle-import") (part "TPTP10R"))
    )
    (comp (ref "U1")
      (value "TLV431DCK")
      (footprint "eagle-import:SOT65P210X110-6N")
      (libsource (lib "eagle-import") (part "TLV431DCK"))
    )
    (comp (ref "U2")
      (value "TLV431DCK")
      (footprint "eagle-import:SOT65P210X110-6N")
      (libsource (lib "eagle-import") (part "TLV431DCK"))
    )
    (comp (ref "UNE")
      (value "TS332IQ2T")
      (footprint "eagle-import:DFN200X200X100-9N")
      (libsource (lib "eagle-import") (part "TS332IQ2T"))
    )
    (comp (ref "UNN")
      (value "TS332IQ2T")
      (footprint "eagle-import:DFN200X200X100-9N")
      (libsource (lib "eagle-import") (part "TS332IQ2T"))
    )
    (comp (ref "UNW")
      (value "TS332IQ2T")
      (footprint "eagle-import:DFN200X200X100-9N")
      (libsource (lib "eagle-import") (part "TS332IQ2T"))
    )
    (comp (ref "USE")
      (value "TS332IQ2T")
      (footprint "eagle-import:DFN200X200X100-9N")
      (libsource (lib "eagle-import") (part "TS332IQ2T"))
    )
    (comp (ref "USS")
      (value "TS332IQ2T")
      (footprint "eagle-import:DFN200X200X100-9N")
      (libsource (lib "eagle-import") (part "TS332IQ2T"))
    )
    (comp (ref "USW")
      (value "TS332IQ2T")
      (footprint "eagle-import:DFN200X200X100-9N")
      (libsource (lib "eagle-import") (part "TS332IQ2T"))
    )
  )
  (nets
    (net (code "1") (name "CLK_IN") (class "Default")
      (node (ref "SENSOR") (pin "E30") (pinfunction "CLK_IN_E30") (pintype "input"))
      (node (ref "U6") (pin "12") (pinfunction "B1_12") (pintype "bidirectional"))
    )
    (net (code "2") (name "FRAME_REQ") (class "Default")
      (node (ref "SENSOR") (pin "G30") (pinfunction "FRAME_REQ_G30") (pintype "input"))
      (node (ref "U5") (pin "11") (pinfunction "B2_11") (pintype "bidirectional"))
    )
    (net (code "3") (name "GND") (class "Default")
      (node (ref "C1") (pin "2") (pinfunction "2_2") (pintype "passive"))
      (node (ref "C10") (pin "2") (pinfunction "2_2") (pintype "passive"))
      (node (ref "C11") (pin "2") (pinfunction "2_2") (pintype "passive"))
      (node (ref "C12") (pin "2") (pinfunction "2_2") (pintype "passive"))
      (node (ref "C13") (pin "2") (pinfunction "2_2") (pintype "passive"))
      (node (ref "C14") (pin "2") (pinfunction "2_2") (pintype "passive"))
      (node (ref "C15") (pin "2") (pinfunction "2_2") (pintype "passive"))
      (node (ref "C16") (pin "2") (pinfunction "2_2") (pintype "passive"))
      (node (ref "C17") (pin "2") (pinfunction "2_2") (pintype "passive"))
      (node (ref "C18") (pin "2") (pinfunction "2_2") (pintype "passive"))
      (node (ref "C19") (pin "2") (pinfunction "2_2") (pintype "passive"))
      (node (ref "C2") (pin "2") (pinfunction "2_2") (pintype "passive"))
      (node (ref "C20") (pin "2") (pinfunction "2_2") (pintype "passive"))
      (node (ref "C21") (pin "2") (pinfunction "2_2") (pintype "passive"))
      (node (ref "C29") (pin "2") (pinfunction "2_2") (pintype "passive"))
      (node (ref "C3") (pin "2") (pinfunction "2_2") (pintype "passive"))
      (node (ref "C30") (pin "2") (pinfunction "2_2") (pintype "passive"))
      (node (ref "C31") (pin "2") (pinfunction "2_2") (pintype "passive"))
      (node (ref "C32") (pin "2") (pinfunction "2_2") (pintype "passive"))
      (node (ref "C33") (pin "2") (pinfunction "2_2") (pintype "passive"))
      (node (ref "C34") (pin "2") (pinfunction "2_2") (pintype "passive"))
      (node (ref "C35") (pin "2") (pinfunction "2_2") (pintype "passive"))
      (node (ref "C36") (pin "2") (pinfunction "2_2") (pintype "passive"))
      (node (ref "C37") (pin "2") (pinfunction "2_2") (pintype "passive"))
      (node (ref "C38") (pin "2") (pinfunction "2_2") (pintype "passive"))
      (node (ref "C39") (pin "2") (pinfunction "2_2") (pintype "passive"))
      (node (ref "C4") (pin "2") (pinfunction "2_2") (pintype "passive"))
      (node (ref "C40") (pin "2") (pinfunction "2_2") (pintype "passive"))
      (node (ref "C41") (pin "2") (pinfunction "2_2") (pintype "passive"))
      (node (ref "C42") (pin "2") (pinfunction "2_2") (pintype "passive"))
      (node (ref "C43") (pin "2") (pinfunction "2_2") (pintype "passive"))
      (node (ref "C44") (pin "2") (pinfunction "2_2") (pintype "passive"))
      (node (ref "C45") (pin "2") (pinfunction "2_2") (pintype "passive"))
      (node (ref "C46") (pin "2") (pinfunction "2_2") (pintype "passive"))
      (node (ref "C47") (pin "2") (pinfunction "2_2") (pintype "passive"))
      (node (ref "C48") (pin "2") (pinfunction "2_2") (pintype "passive"))
      (node (ref "C49") (pin "2") (pinfunction "2_2") (pintype "passive"))
      (node (ref "C5") (pin "2") (pinfunction "2_2") (pintype "passive"))
      (node (ref "C50") (pin "2") (pinfunction "2_2") (pintype "passive"))
      (node (ref "C51") (pin "2") (pinfunction "2_2") (pintype "passive"))
      (node (ref "C52") (pin "2") (pinfunction "2_2") (pintype "passive"))
      (node (ref "C53") (pin "2") (pinfunction "2_2") (pintype "passive"))
      (node (ref "C54") (pin "2") (pinfunction "2_2") (pintype "passive"))
      (node (ref "C55") (pin "2") (pinfunction "2_2") (pintype "passive"))
      (node (ref "C56") (pin "2") (pinfunction "2_2") (pintype "passive"))
      (node (ref "C57") (pin "2") (pinfunction "2_2") (pintype "passive"))
      (node (ref "C58") (pin "2") (pinfunction "2_2") (pintype "passive"))
      (node (ref "C59") (pin "2") (pinfunction "2_2") (pintype "passive"))
      (node (ref "C6") (pin "2") (pinfunction "2_2") (pintype "passive"))
      (node (ref "C60") (pin "2") (pinfunction "2_2") (pintype "passive"))
      (node (ref "C61") (pin "2") (pinfunction "2_2") (pintype "passive"))
      (node (ref "C62") (pin "2") (pinfunction "2_2") (pintype "passive"))
      (node (ref "C63") (pin "2") (pinfunction "2_2") (pintype "passive"))
      (node (ref "C64") (pin "2") (pinfunction "2_2") (pintype "passive"))
      (node (ref "C65") (pin "2") (pinfunction "2_2") (pintype "passive"))
      (node (ref "C66") (pin "2") (pinfunction "2_2") (pintype "passive"))
      (node (ref "C67") (pin "2") (pinfunction "2_2") (pintype "passive"))
      (node (ref "C68") (pin "2") (pinfunction "2_2") (pintype "passive"))
      (node (ref "C69") (pin "2") (pinfunction "2_2") (pintype "passive"))
      (node (ref "C7") (pin "2") (pinfunction "2_2") (pintype "passive"))
      (node (ref "C70") (pin "2") (pinfunction "2_2") (pintype "passive"))
      (node (ref "C71") (pin "2") (pinfunction "2_2") (pintype "passive"))
      (node (ref "C72") (pin "2") (pinfunction "2_2") (pintype "passive"))
      (node (ref "C73") (pin "2") (pinfunction "2_2") (pintype "passive"))
      (node (ref "C74") (pin "2") (pinfunction "2_2") (pintype "passive"))
      (node (ref "C75") (pin "2") (pinfunction "2_2") (pintype "passive"))
      (node (ref "C76") (pin "2") (pinfunction "2_2") (pintype "passive"))
      (node (ref "C77") (pin "2") (pinfunction "2_2") (pintype "passive"))
      (node (ref "C78") (pin "2") (pinfunction "2_2") (pintype "passive"))
      (node (ref "C79") (pin "2") (pinfunction "2_2") (pintype "passive"))
      (node (ref "C8") (pin "2") (pinfunction "2_2") (pintype "passive"))
      (node (ref "C80") (pin "2") (pinfunction "2_2") (pintype "passive"))
      (node (ref "C81") (pin "2") (pinfunction "2_2") (pintype "passive"))
      (node (ref "C82") (pin "2") (pinfunction "2_2") (pintype "passive"))
      (node (ref "C83") (pin "2") (pinfunction "2_2") (pintype "passive"))
      (node (ref "C84") (pin "2") (pinfunction "2_2") (pintype "passive"))
      (node (ref "C85") (pin "2") (pinfunction "2_2") (pintype "passive"))
      (node (ref "C86") (pin "2") (pinfunction "2_2") (pintype "passive"))
      (node (ref "C87") (pin "2") (pinfunction "2_2") (pintype "passive"))
      (node (ref "C88") (pin "2") (pinfunction "2_2") (pintype "passive"))
      (node (ref "C89") (pin "2") (pinfunction "2_2") (pintype "passive"))
      (node (ref "C9") (pin "2") (pinfunction "2_2") (pintype "passive"))
      (node (ref "C90") (pin "2") (pinfunction "2_2") (pintype "passive"))
      (node (ref "C91") (pin "1") (pinfunction "1_1") (pintype "passive"))
      (node (ref "C92") (pin "2") (pinfunction "2_2") (pintype "passive"))
      (node (ref "C93") (pin "2") (pinfunction "2_2") (pintype "passive"))
      (node (ref "GND") (pin "TP") (pinfunction "TP_TP") (pintype "input"))
      (node (ref "GND75") (pin "TP") (pinfunction "TP_TP") (pintype "input"))
      (node (ref "GND77") (pin "TP") (pinfunction "TP_TP") (pintype "input"))
      (node (ref "R12") (pin "2") (pinfunction "2_2") (pintype "passive"))
      (node (ref "R15") (pin "2") (pinfunction "2_2") (pintype "passive"))
      (node (ref "R18") (pin "2") (pinfunction "2_2") (pintype "passive"))
      (node (ref "R22") (pin "1") (pinfunction "1_1") (pintype "passive"))
      (node (ref "R2X") (pin "2") (pinfunction "2_2") (pintype "passive"))
      (node (ref "R3") (pin "2") (pinfunction "2_2") (pintype "passive"))
      (node (ref "R6") (pin "2") (pinfunction "2_2") (pintype "passive"))
      (node (ref "R9") (pin "2") (pinfunction "2_2") (pintype "passive"))
      (node (ref "SENSOR") (pin "A21") (pinfunction "GND_A21") (pintype "power_in"))
      (node (ref "SENSOR") (pin "A25") (pinfunction "GND_A25") (pintype "power_in"))
      (node (ref "SENSOR") (pin "A28") (pinfunction "GND_A28") (pintype "power_in"))
      (node (ref "SENSOR") (pin "A29") (pinfunction "GND_A29") (pintype "power_in"))
      (node (ref "SENSOR") (pin "A9") (pinfunction "GND_A9") (pintype "power_in"))
      (node (ref "SENSOR") (pin "B22") (pinfunction "GND_B22") (pintype "power_in"))
      (node (ref "SENSOR") (pin "B26") (pinfunction "GND_B26") (pintype "power_in"))
      (node (ref "SENSOR") (pin "B27") (pinfunction "GND_B27") (pintype "power_in"))
      (node (ref "SENSOR") (pin "B28") (pinfunction "GND_B28") (pintype "power_in"))
      (node (ref "SENSOR") (pin "B5") (pinfunction "GND_B5") (pintype "power_in"))
      (node (ref "SENSOR") (pin "C15") (pinfunction "GND_C15") (pintype "power_in"))
      (node (ref "SENSOR") (pin "C16") (pinfunction "GND_C16") (pintype "power_in"))
      (node (ref "SENSOR") (pin "C28") (pinfunction "GND_C28") (pintype "power_in"))
      (node (ref "SENSOR") (pin "D2") (pinfunction "GND_D2") (pintype "power_in"))
      (node (ref "SENSOR") (pin "D25") (pinfunction "GND_D25") (pintype "power_in"))
      (node (ref "SENSOR") (pin "D27") (pinfunction "GND_D27") (pintype "power_in"))
      (node (ref "SENSOR") (pin "D29") (pinfunction "GND_D29") (pintype "power_in"))
      (node (ref "SENSOR") (pin "E15") (pinfunction "GND_E15") (pintype "power_in"))
      (node (ref "SENSOR") (pin "E16") (pinfunction "GND_E16") (pintype "power_in"))
      (node (ref "SENSOR") (pin "E25") (pinfunction "GND_E25") (pintype "power_in"))
      (node (ref "SENSOR") (pin "E27") (pinfunction "GND_E27") (pintype "power_in"))
      (node (ref "SENSOR") (pin "E3") (pinfunction "GND_E3") (pintype "power_in"))
      (node (ref "SENSOR") (pin "E4") (pinfunction "DIO2_E4") (pintype "output"))
      (node (ref "SENSOR") (pin "F27") (pinfunction "GND_F27") (pintype "power_in"))
      (node (ref "SENSOR") (pin "F4") (pinfunction "DIO1_F4") (pintype "output"))
      (node (ref "SENSOR") (pin "G3") (pinfunction "DIO4_G3") (pintype "output"))
      (node (ref "SENSOR") (pin "G5") (pinfunction "GND_G5") (pintype "power_in"))
      (node (ref "SENSOR") (pin "H1") (pinfunction "GND_H1") (pintype "power_in"))
      (node (ref "SENSOR") (pin "H21") (pinfunction "GND_H21") (pintype "power_in"))
      (node (ref "SENSOR") (pin "H25") (pinfunction "GND_H25") (pintype "power_in"))
      (node (ref "SENSOR") (pin "H27") (pinfunction "GND_H27") (pintype "power_in"))
      (node (ref "SENSOR") (pin "H4") (pinfunction "DIO3_H4") (pintype "output"))
      (node (ref "SENSOR") (pin "H6") (pinfunction "GND_H6") (pintype "power_in"))
      (node (ref "SENSOR") (pin "H9") (pinfunction "GND_H9") (pintype "power_in"))
      (node (ref "U1") (pin "6") (pinfunction "ANODE_6") (pintype "input"))
      (node (ref "U2") (pin "6") (pinfunction "ANODE_6") (pintype "input"))
      (node (ref "U3") (pin "2") (pinfunction "GND_2") (pintype "power_in"))
      (node (ref "U3") (pin "EP") (pinfunction "EP_EP") (pintype "power_in"))
      (node (ref "U4") (pin "16") (pinfunction "DIR2_16") (pintype "input"))
      (node (ref "U4") (pin "7") (pinfunction "~{OE}_7") (pintype "input"))
      (node (ref "U4") (pin "8") (pinfunction "GND_8") (pintype "passive"))
      (node (ref "U5") (pin "6") (pinfunction "DIR4_6") (pintype "input"))
      (node (ref "U5") (pin "7") (pinfunction "~{OE}_7") (pintype "input"))
      (node (ref "U5") (pin "8") (pinfunction "GND_8") (pintype "passive"))
      (node (ref "U6") (pin "16") (pinfunction "DIR2_16") (pintype "input"))
      (node (ref "U6") (pin "7") (pinfunction "~{OE}_7") (pintype "input"))
      (node (ref "U6") (pin "8") (pinfunction "GND_8") (pintype "passive"))
      (node (ref "U7") (pin "4") (pinfunction "GND_4") (pintype "power_in"))
      (node (ref "U7") (pin "5") (pinfunction "A2_5") (pintype "input"))
      (node (ref "U7") (pin "6") (pinfunction "A1_6") (pintype "input"))
      (node (ref "U7") (pin "7") (pinfunction "A0_7") (pintype "input"))
      (node (ref "UEP") (pin "1") (pinfunction "A0_1") (pintype "input"))
      (node (ref "UEP") (pin "2") (pinfunction "A1_2") (pintype "input"))
      (node (ref "UEP") (pin "3") (pinfunction "A2_3") (pintype "input"))
      (node (ref "UEP") (pin "4") (pinfunction "GND_4") (pintype "passive"))
      (node (ref "UEP") (pin "EP") (pinfunction "EP_EP") (pintype "passive"))
      (node (ref "UNE") (pin "4") (pinfunction "VSS_4") (pintype "power_in"))
      (node (ref "UNE") (pin "EP") (pinfunction "EP_EP") (pintype "passive"))
      (node (ref "UNN") (pin "4") (pinfunction "VSS_4") (pintype "power_in"))
      (node (ref "UNN") (pin "EP") (pinfunction "EP_EP") (pintype "passive"))
      (node (ref "UNW") (pin "4") (pinfunction "VSS_4") (pintype "power_in"))
      (node (ref "UNW") (pin "EP") (pinfunction "EP_EP") (pintype "passive"))
      (node (ref "USE") (pin "4") (pinfunction "VSS_4") (pintype "power_in"))
      (node (ref "USE") (pin "EP") (pinfunction "EP_EP") (pintype "passive"))
      (node (ref "USS") (pin "4") (pinfunction "VSS_4") (pintype "power_in"))
      (node (ref "USS") (pin "EP") (pinfunction "EP_EP") (pintype "passive"))
      (node (ref "USW") (pin "4") (pinfunction "VSS_4") (pintype "power_in"))
      (node (ref "USW") (pin "EP") (pinfunction "EP_EP") (pintype "passive"))
      (node (ref "X-NORTH") (pin "102") (pinfunction "102_102") (pintype "bidirectional"))
      (node (ref "X-NORTH") (pin "103") (pinfunction "103_103") (pintype "bidirectional"))
      (node (ref "X-NORTH") (pin "108") (pinfunction "108_108") (pintype "bidirectional"))
      (node (ref "X-NORTH") (pin "114") (pinfunction "114_114") (pintype "bidirectional"))
      (node (ref "X-NORTH") (pin "12") (pinfunction "12_12") (pintype "bidirectional"))
      (node (ref "X-NORTH") (pin "120") (pinfunction "120_120") (pintype "bidirectional"))
      (node (ref "X-NORTH") (pin "126") (pinfunction "126_126") (pintype "bidirectional"))
      (node (ref "X-NORTH") (pin "132") (pinfunction "132_132") (pintype "bidirectional"))
      (node (ref "X-NORTH") (pin "138") (pinfunction "138_138") (pintype "bidirectional"))
      (node (ref "X-NORTH") (pin "139") (pinfunction "139_139") (pintype "bidirectional"))
      (node (ref "X-NORTH") (pin "18") (pinfunction "18_18") (pintype "bidirectional"))
      (node (ref "X-NORTH") (pin "24") (pinfunction "24_24") (pintype "bidirectional"))
      (node (ref "X-NORTH") (pin "30") (pinfunction "30_30") (pintype "bidirectional"))
      (node (ref "X-NORTH") (pin "36") (pinfunction "36_36") (pintype "bidirectional"))
      (node (ref "X-NORTH") (pin "42") (pinfunction "42_42") (pintype "bidirectional"))
      (node (ref "X-NORTH") (pin "43") (pinfunction "43_43") (pintype "bidirectional"))
      (node (ref "X-NORTH") (pin "48") (pinfunction "48_48") (pintype "bidirectional"))
      (node (ref "X-NORTH") (pin "54") (pinfunction "54_54") (pintype "bidirectional"))
      (node (ref "X-NORTH") (pin "60") (pinfunction "60_60") (pintype "bidirectional"))
      (node (ref "X-NORTH") (pin "66") (pinfunction "66_66") (pintype "bidirectional"))
      (node (ref "X-NORTH") (pin "72") (pinfunction "72_72") (pintype "bidirectional"))
      (node (ref "X-NORTH") (pin "78") (pinfunction "78_78") (pintype "bidirectional"))
      (node (ref "X-NORTH") (pin "84") (pinfunction "84_84") (pintype "bidirectional"))
      (node (ref "X-NORTH") (pin "90") (pinfunction "90_90") (pintype "bidirectional"))
      (node (ref "X-NORTH") (pin "96") (pinfunction "96_96") (pintype "bidirectional"))
      (node (ref "X-SOUTH") (pin "102") (pinfunction "102_102") (pintype "bidirectional"))
      (node (ref "X-SOUTH") (pin "103") (pinfunction "103_103") (pintype "bidirectional"))
      (node (ref "X-SOUTH") (pin "108") (pinfunction "108_108") (pintype "bidirectional"))
      (node (ref "X-SOUTH") (pin "114") (pinfunction "114_114") (pintype "bidirectional"))
      (node (ref "X-SOUTH") (pin "12") (pinfunction "12_12") (pintype "bidirectional"))
      (node (ref "X-SOUTH") (pin "120") (pinfunction "120_120") (pintype "bidirectional"))
      (node (ref "X-SOUTH") (pin "126") (pinfunction "126_126") (pintype "bidirectional"))
      (node (ref "X-SOUTH") (pin "132") (pinfunction "132_132") (pintype "bidirectional"))
      (node (ref "X-SOUTH") (pin "138") (pinfunction "138_138") (pintype "bidirectional"))
      (node (ref "X-SOUTH") (pin "139") (pinfunction "139_139") (pintype "bidirectional"))
      (node (ref "X-SOUTH") (pin "18") (pinfunction "18_18") (pintype "bidirectional"))
      (node (ref "X-SOUTH") (pin "24") (pinfunction "24_24") (pintype "bidirectional"))
      (node (ref "X-SOUTH") (pin "30") (pinfunction "30_30") (pintype "bidirectional"))
      (node (ref "X-SOUTH") (pin "36") (pinfunction "36_36") (pintype "bidirectional"))
      (node (ref "X-SOUTH") (pin "42") (pinfunction "42_42") (pintype "bidirectional"))
      (node (ref "X-SOUTH") (pin "43") (pinfunction "43_43") (pintype "bidirectional"))
      (node (ref "X-SOUTH") (pin "48") (pinfunction "48_48") (pintype "bidirectional"))
      (node (ref "X-SOUTH") (pin "54") (pinfunction "54_54") (pintype "bidirectional"))
      (node (ref "X-SOUTH") (pin "60") (pinfunction "60_60") (pintype "bidirectional"))
      (node (ref "X-SOUTH") (pin "66") (pinfunction "66_66") (pintype "bidirectional"))
      (node (ref "X-SOUTH") (pin "72") (pinfunction "72_72") (pintype "bidirectional"))
      (node (ref "X-SOUTH") (pin "78") (pinfunction "78_78") (pintype "bidirectional"))
      (node (ref "X-SOUTH") (pin "84") (pinfunction "84_84") (pintype "bidirectional"))
      (node (ref "X-SOUTH") (pin "90") (pinfunction "90_90") (pintype "bidirectional"))
      (node (ref "X-SOUTH") (pin "96") (pinfunction "96_96") (pintype "bidirectional"))
    )
    (net (code "4") (name "N$42") (class "Default")
      (node (ref "SENSOR") (pin "A2") (pinfunction "TANA_A2") (pintype "output"))
    )
    (net (code "5") (name "N00_N") (class "Default")
      (node (ref "R25") (pin "2") (pinfunction "2_2") (pintype "passive"))
      (node (ref "SENSOR") (pin "E6") (pinfunction "LVDS_CLK_P_E6") (pintype "input"))
      (node (ref "X-NORTH") (pin "16") (pinfunction "16_16") (pintype "bidirectional"))
    )
    (net (code "6") (name "N00_P") (class "Default")
      (node (ref "R25") (pin "1") (pinfunction "1_1") (pintype "passive"))
      (node (ref "SENSOR") (pin "E5") (pinfunction "LVDS_CLK_N_E5") (pintype "input"))
      (node (ref "X-NORTH") (pin "14") (pinfunction "14_14") (pintype "bidirectional"))
    )
    (net (code "7") (name "N01_N") (class "Default")
      (node (ref "SENSOR") (pin "G7") (pinfunction "OUTCLK_P_G7") (pintype "output"))
      (node (ref "X-NORTH") (pin "17") (pinfunction "17_17") (pintype "bidirectional"))
    )
    (net (code "8") (name "N01_P") (class "Default")
      (node (ref "SENSOR") (pin "G6") (pinfunction "OUTCLK_N_G6") (pintype "output"))
      (node (ref "X-NORTH") (pin "15") (pinfunction "15_15") (pintype "bidirectional"))
    )
    (net (code "9") (name "N02_N") (class "Default")
      (node (ref "SENSOR") (pin "F7") (pinfunction "OUT33_P_F7") (pintype "output"))
      (node (ref "X-NORTH") (pin "22") (pinfunction "22_22") (pintype "bidirectional"))
    )
    (net (code "10") (name "N02_P") (class "Default")
      (node (ref "SENSOR") (pin "F6") (pinfunction "OUT33_N_F6") (pintype "output"))
      (node (ref "X-NORTH") (pin "20") (pinfunction "20_20") (pintype "bidirectional"))
    )
    (net (code "11") (name "N03_N") (class "Default")
      (node (ref "X-NORTH") (pin "23") (pinfunction "23_23") (pintype "bidirectional"))
    )
    (net (code "12") (name "N03_P") (class "Default")
      (node (ref "X-NORTH") (pin "21") (pinfunction "21_21") (pintype "bidirectional"))
    )
    (net (code "13") (name "N04_N") (class "Default")
      (node (ref "SENSOR") (pin "E8") (pinfunction "OUT35_P_E8") (pintype "output"))
      (node (ref "X-NORTH") (pin "28") (pinfunction "28_28") (pintype "bidirectional"))
    )
    (net (code "14") (name "N04_P") (class "Default")
      (node (ref "SENSOR") (pin "E7") (pinfunction "OUT35_N_E7") (pintype "output"))
      (node (ref "X-NORTH") (pin "26") (pinfunction "26_26") (pintype "bidirectional"))
    )
    (net (code "15") (name "N05_N") (class "Default")
      (node (ref "SENSOR") (pin "H8") (pinfunction "OUT34_P_H8") (pintype "output"))
      (node (ref "X-NORTH") (pin "29") (pinfunction "29_29") (pintype "bidirectional"))
    )
    (net (code "16") (name "N05_P") (class "Default")
      (node (ref "SENSOR") (pin "H7") (pinfunction "OUT34_N_H7") (pintype "output"))
      (node (ref "X-NORTH") (pin "27") (pinfunction "27_27") (pintype "bidirectional"))
    )
    (net (code "17") (name "N06_N") (class "Default")
      (node (ref "SENSOR") (pin "F9") (pinfunction "OUT37_P_F9") (pintype "output"))
      (node (ref "X-NORTH") (pin "34") (pinfunction "34_34") (pintype "bidirectional"))
    )
    (net (code "18") (name "N06_P") (class "Default")
      (node (ref "SENSOR") (pin "F8") (pinfunction "OUT37_N_F8") (pintype "output"))
      (node (ref "X-NORTH") (pin "32") (pinfunction "32_32") (pintype "bidirectional"))
    )
    (net (code "19") (name "N07_N") (class "Default")
      (node (ref "SENSOR") (pin "G9") (pinfunction "OUT36_P_G9") (pintype "output"))
      (node (ref "X-NORTH") (pin "35") (pinfunction "35_35") (pintype "bidirectional"))
    )
    (net (code "20") (name "N07_P") (class "Default")
      (node (ref "SENSOR") (pin "G8") (pinfunction "OUT36_N_G8") (pintype "output"))
      (node (ref "X-NORTH") (pin "33") (pinfunction "33_33") (pintype "bidirectional"))
    )
    (net (code "21") (name "N08_N") (class "Default")
      (node (ref "SENSOR") (pin "E10") (pinfunction "OUT38_P_E10") (pintype "output"))
      (node (ref "X-NORTH") (pin "40") (pinfunction "40_40") (pintype "bidirectional"))
    )
    (net (code "22") (name "N08_P") (class "Default")
      (node (ref "SENSOR") (pin "E9") (pinfunction "OUT38_N_E9") (pintype "output"))
      (node (ref "X-NORTH") (pin "38") (pinfunction "38_38") (pintype "bidirectional"))
    )
    (net (code "23") (name "N09_N") (class "Default")
      (node (ref "SENSOR") (pin "G11") (pinfunction "OUT39_P_G11") (pintype "output"))
      (node (ref "X-NORTH") (pin "41") (pinfunction "41_41") (pintype "bidirectional"))
    )
    (net (code "24") (name "N09_P") (class "Default")
      (node (ref "SENSOR") (pin "G10") (pinfunction "OUT39_N_G10") (pintype "output"))
      (node (ref "X-NORTH") (pin "39") (pinfunction "39_39") (pintype "bidirectional"))
    )
    (net (code "25") (name "N10_N") (class "Default")
      (node (ref "SENSOR") (pin "F11") (pinfunction "OUT40_P_F11") (pintype "output"))
      (node (ref "X-NORTH") (pin "46") (pinfunction "46_46") (pintype "bidirectional"))
    )
    (net (code "26") (name "N10_P") (class "Default")
      (node (ref "SENSOR") (pin "F10") (pinfunction "OUT40_N_F10") (pintype "output"))
      (node (ref "X-NORTH") (pin "44") (pinfunction "44_44") (pintype "bidirectional"))
    )
    (net (code "27") (name "N11_N") (class "Default")
      (node (ref "SENSOR") (pin "H12") (pinfunction "OUT41_P_H12") (pintype "output"))
      (node (ref "X-NORTH") (pin "47") (pinfunction "47_47") (pintype "bidirectional"))
    )
    (net (code "28") (name "N11_P") (class "Default")
      (node (ref "SENSOR") (pin "H11") (pinfunction "OUT41_N_H11") (pintype "output"))
      (node (ref "X-NORTH") (pin "45") (pinfunction "45_45") (pintype "bidirectional"))
    )
    (net (code "29") (name "N12_N") (class "Default")
      (node (ref "SENSOR") (pin "E12") (pinfunction "OUT42_P_E12") (pintype "output"))
      (node (ref "X-NORTH") (pin "52") (pinfunction "52_52") (pintype "bidirectional"))
    )
    (net (code "30") (name "N12_P") (class "Default")
      (node (ref "SENSOR") (pin "E11") (pinfunction "OUT42_N_E11") (pintype "output"))
      (node (ref "X-NORTH") (pin "50") (pinfunction "50_50") (pintype "bidirectional"))
    )
    (net (code "31") (name "N13_N") (class "Default")
      (node (ref "SENSOR") (pin "G13") (pinfunction "OUT43_P_G13") (pintype "output"))
      (node (ref "X-NORTH") (pin "53") (pinfunction "53_53") (pintype "bidirectional"))
    )
    (net (code "32") (name "N13_P") (class "Default")
      (node (ref "SENSOR") (pin "G12") (pinfunction "OUT43_N_G12") (pintype "output"))
      (node (ref "X-NORTH") (pin "51") (pinfunction "51_51") (pintype "bidirectional"))
    )
    (net (code "33") (name "N14_N") (class "Default")
      (node (ref "SENSOR") (pin "F13") (pinfunction "OUT44_P_F13") (pintype "output"))
      (node (ref "X-NORTH") (pin "58") (pinfunction "58_58") (pintype "bidirectional"))
    )
    (net (code "34") (name "N14_P") (class "Default")
      (node (ref "SENSOR") (pin "F12") (pinfunction "OUT44_N_F12") (pintype "output"))
      (node (ref "X-NORTH") (pin "56") (pinfunction "56_56") (pintype "bidirectional"))
    )
    (net (code "35") (name "N15_N") (class "Default")
      (node (ref "SENSOR") (pin "H14") (pinfunction "OUT45_P_H14") (pintype "output"))
      (node (ref "X-NORTH") (pin "59") (pinfunction "59_59") (pintype "bidirectional"))
    )
    (net (code "36") (name "N15_P") (class "Default")
      (node (ref "SENSOR") (pin "H13") (pinfunction "OUT45_N_H13") (pintype "output"))
      (node (ref "X-NORTH") (pin "57") (pinfunction "57_57") (pintype "bidirectional"))
    )
    (net (code "37") (name "N16_N") (class "Default")
      (node (ref "SENSOR") (pin "E14") (pinfunction "OUT46_P_E14") (pintype "output"))
      (node (ref "X-NORTH") (pin "64") (pinfunction "64_64") (pintype "bidirectional"))
    )
    (net (code "38") (name "N16_P") (class "Default")
      (node (ref "SENSOR") (pin "E13") (pinfunction "OUT46_N_E13") (pintype "output"))
      (node (ref "X-NORTH") (pin "62") (pinfunction "62_62") (pintype "bidirectional"))
    )
    (net (code "39") (name "N17_N") (class "Default")
      (node (ref "SENSOR") (pin "G15") (pinfunction "OUT47_P_G15") (pintype "output"))
      (node (ref "X-NORTH") (pin "65") (pinfunction "65_65") (pintype "bidirectional"))
    )
    (net (code "40") (name "N17_P") (class "Default")
      (node (ref "SENSOR") (pin "G14") (pinfunction "OUT47_N_G14") (pintype "output"))
      (node (ref "X-NORTH") (pin "63") (pinfunction "63_63") (pintype "bidirectional"))
    )
    (net (code "41") (name "N18_N") (class "Default")
      (node (ref "SENSOR") (pin "F15") (pinfunction "OUT48_P_F15") (pintype "output"))
      (node (ref "X-NORTH") (pin "70") (pinfunction "70_70") (pintype "bidirectional"))
    )
    (net (code "42") (name "N18_P") (class "Default")
      (node (ref "SENSOR") (pin "F14") (pinfunction "OUT48_N_F14") (pintype "output"))
      (node (ref "X-NORTH") (pin "68") (pinfunction "68_68") (pintype "bidirectional"))
    )
    (net (code "43") (name "N19_N") (class "Default")
      (node (ref "SENSOR") (pin "G17") (pinfunction "OUT50_P_G17") (pintype "output"))
      (node (ref "X-NORTH") (pin "71") (pinfunction "71_71") (pintype "bidirectional"))
    )
    (net (code "44") (name "N19_P") (class "Default")
      (node (ref "SENSOR") (pin "G16") (pinfunction "OUT50_N_G16") (pintype "output"))
      (node (ref "X-NORTH") (pin "69") (pinfunction "69_69") (pintype "bidirectional"))
    )
    (net (code "45") (name "N20_N") (class "Default")
      (node (ref "SENSOR") (pin "F17") (pinfunction "OUT49_P_F17") (pintype "output"))
      (node (ref "X-NORTH") (pin "76") (pinfunction "76_76") (pintype "bidirectional"))
    )
    (net (code "46") (name "N20_P") (class "Default")
      (node (ref "SENSOR") (pin "F16") (pinfunction "OUT49_N_F16") (pintype "output"))
      (node (ref "X-NORTH") (pin "74") (pinfunction "74_74") (pintype "bidirectional"))
    )
    (net (code "47") (name "N21_N") (class "Default")
      (node (ref "SENSOR") (pin "H18") (pinfunction "OUT52_P_H18") (pintype "output"))
      (node (ref "X-NORTH") (pin "77") (pinfunction "77_77") (pintype "bidirectional"))
    )
    (net (code "48") (name "N21_P") (class "Default")
      (node (ref "SENSOR") (pin "H17") (pinfunction "OUT52_N_H17") (pintype "output"))
      (node (ref "X-NORTH") (pin "75") (pinfunction "75_75") (pintype "bidirectional"))
    )
    (net (code "49") (name "N22_N") (class "Default")
      (node (ref "SENSOR") (pin "E18") (pinfunction "OUT51_P_E18") (pintype "output"))
      (node (ref "X-NORTH") (pin "82") (pinfunction "82_82") (pintype "bidirectional"))
    )
    (net (code "50") (name "N22_P") (class "Default")
      (node (ref "SENSOR") (pin "E17") (pinfunction "OUT51_N_E17") (pintype "output"))
      (node (ref "X-NORTH") (pin "80") (pinfunction "80_80") (pintype "bidirectional"))
    )
    (net (code "51") (name "N23_N") (class "Default")
      (node (ref "SENSOR") (pin "G19") (pinfunction "OUT54_P_G19") (pintype "output"))
      (node (ref "X-NORTH") (pin "83") (pinfunction "83_83") (pintype "bidirectional"))
    )
    (net (code "52") (name "N23_P") (class "Default")
      (node (ref "SENSOR") (pin "G18") (pinfunction "OUT54_N_G18") (pintype "output"))
      (node (ref "X-NORTH") (pin "81") (pinfunction "81_81") (pintype "bidirectional"))
    )
    (net (code "53") (name "N24_N") (class "Default")
      (node (ref "SENSOR") (pin "F19") (pinfunction "OUT53_P_F19") (pintype "output"))
      (node (ref "X-NORTH") (pin "88") (pinfunction "88_88") (pintype "bidirectional"))
    )
    (net (code "54") (name "N24_P") (class "Default")
      (node (ref "SENSOR") (pin "F18") (pinfunction "OUT53_N_F18") (pintype "output"))
      (node (ref "X-NORTH") (pin "86") (pinfunction "86_86") (pintype "bidirectional"))
    )
    (net (code "55") (name "N25_N") (class "Default")
      (node (ref "SENSOR") (pin "H20") (pinfunction "OUT56_P_H20") (pintype "output"))
      (node (ref "X-NORTH") (pin "89") (pinfunction "89_89") (pintype "bidirectional"))
    )
    (net (code "56") (name "N25_P") (class "Default")
      (node (ref "SENSOR") (pin "H19") (pinfunction "OUT56_N_H19") (pintype "output"))
      (node (ref "X-NORTH") (pin "87") (pinfunction "87_87") (pintype "bidirectional"))
    )
    (net (code "57") (name "N26_N") (class "Default")
      (node (ref "SENSOR") (pin "E20") (pinfunction "OUT55_P_E20") (pintype "output"))
      (node (ref "X-NORTH") (pin "94") (pinfunction "94_94") (pintype "bidirectional"))
    )
    (net (code "58") (name "N26_P") (class "Default")
      (node (ref "SENSOR") (pin "E19") (pinfunction "OUT55_N_E19") (pintype "output"))
      (node (ref "X-NORTH") (pin "92") (pinfunction "92_92") (pintype "bidirectional"))
    )
    (net (code "59") (name "N27_N") (class "Default")
      (node (ref "SENSOR") (pin "G21") (pinfunction "OUT58_P_G21") (pintype "output"))
      (node (ref "X-NORTH") (pin "95") (pinfunction "95_95") (pintype "bidirectional"))
    )
    (net (code "60") (name "N27_P") (class "Default")
      (node (ref "SENSOR") (pin "G20") (pinfunction "OUT58_N_G20") (pintype "output"))
      (node (ref "X-NORTH") (pin "93") (pinfunction "93_93") (pintype "bidirectional"))
    )
    (net (code "61") (name "N28_N") (class "Default")
      (node (ref "SENSOR") (pin "F21") (pinfunction "OUT57_P_F21") (pintype "output"))
      (node (ref "X-NORTH") (pin "100") (pinfunction "100_100") (pintype "bidirectional"))
    )
    (net (code "62") (name "N28_P") (class "Default")
      (node (ref "SENSOR") (pin "F20") (pinfunction "OUT57_N_F20") (pintype "output"))
      (node (ref "X-NORTH") (pin "98") (pinfunction "98_98") (pintype "bidirectional"))
    )
    (net (code "63") (name "N29_N") (class "Default")
      (node (ref "SENSOR") (pin "G23") (pinfunction "OUT61_P_G23") (pintype "output"))
      (node (ref "X-NORTH") (pin "101") (pinfunction "101_101") (pintype "bidirectional"))
    )
    (net (code "64") (name "N29_P") (class "Default")
      (node (ref "SENSOR") (pin "G22") (pinfunction "OUT61_N_G22") (pintype "output"))
      (node (ref "X-NORTH") (pin "99") (pinfunction "99_99") (pintype "bidirectional"))
    )
    (net (code "65") (name "N30_N") (class "Default")
      (node (ref "SENSOR") (pin "E22") (pinfunction "OUT59_P_E22") (pintype "output"))
      (node (ref "X-NORTH") (pin "106") (pinfunction "106_106") (pintype "bidirectional"))
    )
    (net (code "66") (name "N30_P") (class "Default")
      (node (ref "SENSOR") (pin "E21") (pinfunction "OUT59_N_E21") (pintype "output"))
      (node (ref "X-NORTH") (pin "104") (pinfunction "104_104") (pintype "bidirectional"))
    )
    (net (code "67") (name "N31_N") (class "Default")
      (node (ref "SENSOR") (pin "H24") (pinfunction "OUT63_P_H24") (pintype "output"))
      (node (ref "X-NORTH") (pin "107") (pinfunction "107_107") (pintype "bidirectional"))
    )
    (net (code "68") (name "N31_P") (class "Default")
      (node (ref "SENSOR") (pin "H23") (pinfunction "OUT63_N_H23") (pintype "output"))
      (node (ref "X-NORTH") (pin "105") (pinfunction "105_105") (pintype "bidirectional"))
    )
    (net (code "69") (name "N32_N") (class "Default")
      (node (ref "SENSOR") (pin "F23") (pinfunction "OUT60_P_F23") (pintype "output"))
      (node (ref "X-NORTH") (pin "112") (pinfunction "112_112") (pintype "bidirectional"))
    )
    (net (code "70") (name "N32_P") (class "Default")
      (node (ref "SENSOR") (pin "F22") (pinfunction "OUT60_N_F22") (pintype "output"))
      (node (ref "X-NORTH") (pin "110") (pinfunction "110_110") (pintype "bidirectional"))
    )
    (net (code "71") (name "N33_N") (class "Default")
      (node (ref "SENSOR") (pin "G25") (pinfunction "OUT64_P_G25") (pintype "output"))
      (node (ref "X-NORTH") (pin "113") (pinfunction "113_113") (pintype "bidirectional"))
    )
    (net (code "72") (name "N33_P") (class "Default")
      (node (ref "SENSOR") (pin "G24") (pinfunction "OUT64_N_G24") (pintype "output"))
      (node (ref "X-NORTH") (pin "111") (pinfunction "111_111") (pintype "bidirectional"))
    )
    (net (code "73") (name "N34_N") (class "Default")
      (node (ref "SENSOR") (pin "E24") (pinfunction "OUT62_P_E24") (pintype "output"))
      (node (ref "X-NORTH") (pin "118") (pinfunction "118_118") (pintype "bidirectional"))
    )
    (net (code "74") (name "N34_P") (class "Default")
      (node (ref "SENSOR") (pin "E23") (pinfunction "OUT62_N_E23") (pintype "output"))
      (node (ref "X-NORTH") (pin "116") (pinfunction "116_116") (pintype "bidirectional"))
    )
    (net (code "75") (name "N35_N") (class "Default")
      (node (ref "U6") (pin "4") (pinfunction "A4_4") (pintype "bidirectional"))
      (node (ref "X-NORTH") (pin "119") (pinfunction "119_119") (pintype "bidirectional"))
    )
    (net (code "76") (name "N35_P") (class "Default")
      (node (ref "U6") (pin "3") (pinfunction "A3_3") (pintype "bidirectional"))
      (node (ref "X-NORTH") (pin "117") (pinfunction "117_117") (pintype "bidirectional"))
    )
    (net (code "77") (name "N36_N") (class "Default")
      (node (ref "X-NORTH") (pin "124") (pinfunction "124_124") (pintype "bidirectional"))
    )
    (net (code "78") (name "N36_P") (class "Default")
      (node (ref "X-NORTH") (pin "122") (pinfunction "122_122") (pintype "bidirectional"))
    )
    (net (code "79") (name "N37_N") (class "Default")
      (node (ref "U5") (pin "3") (pinfunction "A3_3") (pintype "bidirectional"))
      (node (ref "X-NORTH") (pin "125") (pinfunction "125_125") (pintype "bidirectional"))
    )
    (net (code "80") (name "N37_P") (class "Default")
      (node (ref "U5") (pin "4") (pinfunction "A4_4") (pintype "bidirectional"))
      (node (ref "X-NORTH") (pin "123") (pinfunction "123_123") (pintype "bidirectional"))
    )
    (net (code "81") (name "N38_N") (class "Default")
      (node (ref "U6") (pin "2") (pinfunction "A2_2") (pintype "bidirectional"))
      (node (ref "X-NORTH") (pin "130") (pinfunction "130_130") (pintype "bidirectional"))
    )
    (net (code "82") (name "N38_P") (class "Default")
      (node (ref "U6") (pin "1") (pinfunction "A1_1") (pintype "bidirectional"))
      (node (ref "X-NORTH") (pin "128") (pinfunction "128_128") (pintype "bidirectional"))
    )
    (net (code "83") (name "N39_N") (class "Default")
      (node (ref "U5") (pin "1") (pinfunction "A1_1") (pintype "bidirectional"))
      (node (ref "X-NORTH") (pin "131") (pinfunction "131_131") (pintype "bidirectional"))
    )
    (net (code "84") (name "N39_P") (class "Default")
      (node (ref "U5") (pin "2") (pinfunction "A2_2") (pintype "bidirectional"))
      (node (ref "X-NORTH") (pin "129") (pinfunction "129_129") (pintype "bidirectional"))
    )
    (net (code "85") (name "N_CHK_EN") (class "Default")
      (node (ref "X-NORTH") (pin "8") (pinfunction "8_8") (pintype "bidirectional"))
    )
    (net (code "86") (name "N_CHK_V") (class "Default")
      (node (ref "C2") (pin "1") (pinfunction "1_1") (pintype "passive"))
      (node (ref "C3") (pin "1") (pinfunction "1_1") (pintype "passive"))
      (node (ref "C4") (pin "1") (pinfunction "1_1") (pintype "passive"))
      (node (ref "R19") (pin "1") (pinfunction "1_1") (pintype "passive"))
      (node (ref "TP1") (pin "TP") (pinfunction "TP_TP") (pintype "input"))
      (node (ref "UNE") (pin "8") (pinfunction "VDD_8") (pintype "power_in"))
      (node (ref "UNN") (pin "8") (pinfunction "VDD_8") (pintype "power_in"))
      (node (ref "UNW") (pin "8") (pinfunction "VDD_8") (pintype "power_in"))
      (node (ref "X-NORTH") (pin "10") (pinfunction "10_10") (pintype "bidirectional"))
    )
    (net (code "87") (name "N_I2C_EN") (class "Default")
      (node (ref "X-NORTH") (pin "137") (pinfunction "137_137") (pintype "bidirectional"))
    )
    (net (code "88") (name "N_I2C_V") (class "Default")
      (node (ref "C1") (pin "1") (pinfunction "1_1") (pintype "passive"))
      (node (ref "R1X") (pin "1") (pinfunction "1_1") (pintype "passive"))
      (node (ref "UEP") (pin "8") (pinfunction "VCC_8") (pintype "power_in"))
      (node (ref "X-NORTH") (pin "135") (pinfunction "135_135") (pintype "bidirectional"))
    )
    (net (code "89") (name "N_REF") (class "Default")
      (node (ref "R19") (pin "2") (pinfunction "2_2") (pintype "passive"))
      (node (ref "TP2") (pin "TP") (pinfunction "TP_TP") (pintype "input"))
      (node (ref "U1") (pin "1") (pinfunction "CATHODE_1") (pintype "output"))
      (node (ref "U1") (pin "3") (pinfunction "REF_3") (pintype "input"))
      (node (ref "UNE") (pin "2") (pinfunction "VINA-_2") (pintype "input"))
      (node (ref "UNE") (pin "5") (pinfunction "VINB+_5") (pintype "input"))
      (node (ref "UNN") (pin "2") (pinfunction "VINA-_2") (pintype "input"))
      (node (ref "UNN") (pin "5") (pinfunction "VINB+_5") (pintype "input"))
      (node (ref "UNW") (pin "2") (pinfunction "VINA-_2") (pintype "input"))
      (node (ref "UNW") (pin "5") (pinfunction "VINB+_5") (pintype "input"))
    )
    (net (code "90") (name "N_SCK") (class "Default")
      (node (ref "U4") (pin "4") (pinfunction "A4_4") (pintype "bidirectional"))
      (node (ref "X-NORTH") (pin "144") (pinfunction "144_144") (pintype "bidirectional"))
    )
    (net (code "91") (name "N_SCL") (class "Default")
      (node (ref "UEP") (pin "6") (pinfunction "SCL_6") (pintype "input"))
      (node (ref "X-NORTH") (pin "143") (pinfunction "143_143") (pintype "bidirectional"))
    )
    (net (code "92") (name "N_SDA") (class "Default")
      (node (ref "UEP") (pin "5") (pinfunction "SDA_5") (pintype "bidirectional"))
      (node (ref "X-NORTH") (pin "141") (pinfunction "141_141") (pintype "bidirectional"))
    )
    (net (code "93") (name "N_SDI") (class "Default")
      (node (ref "U4") (pin "2") (pinfunction "A2_2") (pintype "bidirectional"))
      (node (ref "X-NORTH") (pin "140") (pinfunction "140_140") (pintype "bidirectional"))
    )
    (net (code "94") (name "N_SDO") (class "Default")
      (node (ref "U4") (pin "3") (pinfunction "A3_3") (pintype "bidirectional"))
      (node (ref "X-NORTH") (pin "142") (pinfunction "142_142") (pintype "bidirectional"))
    )
    (net (code "95") (name "N_SPI_EN") (class "Default")
      (node (ref "U4") (pin "1") (pinfunction "A1_1") (pintype "bidirectional"))
      (node (ref "X-NORTH") (pin "136") (pinfunction "136_136") (pintype "bidirectional"))
    )
    (net (code "96") (name "N_SPI_V") (class "Default")
      (node (ref "C59") (pin "1") (pinfunction "1_1") (pintype "passive"))
      (node (ref "U4") (pin "14") (pinfunction "VCCA_14") (pintype "power_in"))
      (node (ref "U4") (pin "15") (pinfunction "DIR1_15") (pintype "input"))
      (node (ref "U4") (pin "5") (pinfunction "DIR3_5") (pintype "input"))
      (node (ref "U4") (pin "6") (pinfunction "DIR4_6") (pintype "input"))
      (node (ref "X-NORTH") (pin "134") (pinfunction "134_134") (pintype "bidirectional"))
    )
    (net (code "97") (name "N_VE") (class "Default")
      (node (ref "C22") (pin "1") (pinfunction "1_1") (pintype "passive"))
      (node (ref "C23") (pin "1") (pinfunction "1_1") (pintype "passive"))
      (node (ref "C24") (pin "1") (pinfunction "1_1") (pintype "passive"))
      (node (ref "C25") (pin "1") (pinfunction "1_1") (pintype "passive"))
      (node (ref "C26") (pin "1") (pinfunction "1_1") (pintype "passive"))
      (node (ref "C27") (pin "1") (pinfunction "1_1") (pintype "passive"))
      (node (ref "C28") (pin "1") (pinfunction "1_1") (pintype "passive"))
      (node (ref "C50") (pin "1") (pinfunction "1_1") (pintype "passive"))
      (node (ref "C51") (pin "1") (pinfunction "1_1") (pintype "passive"))
      (node (ref "C52") (pin "1") (pinfunction "1_1") (pintype "passive"))
      (node (ref "C53") (pin "1") (pinfunction "1_1") (pintype "passive"))
      (node (ref "C54") (pin "1") (pinfunction "1_1") (pintype "passive"))
      (node (ref "C55") (pin "1") (pinfunction "1_1") (pintype "passive"))
      (node (ref "C56") (pin "1") (pinfunction "1_1") (pintype "passive"))
      (node (ref "C67") (pin "1") (pinfunction "1_1") (pintype "passive"))
      (node (ref "C69") (pin "1") (pinfunction "1_1") (pintype "passive"))
      (node (ref "C75") (pin "1") (pinfunction "1_1") (pintype "passive"))
      (node (ref "C76") (pin "1") (pinfunction "1_1") (pintype "passive"))
      (node (ref "C77") (pin "1") (pinfunction "1_1") (pintype "passive"))
      (node (ref "C84") (pin "1") (pinfunction "1_1") (pintype "passive"))
      (node (ref "C85") (pin "1") (pinfunction "1_1") (pintype "passive"))
      (node (ref "C86") (pin "1") (pinfunction "1_1") (pintype "passive"))
      (node (ref "C93") (pin "1") (pinfunction "1_1") (pintype "passive"))
      (node (ref "SENSOR") (pin "C26") (pinfunction "VDD33_C26") (pintype "power_in"))
      (node (ref "SENSOR") (pin "C27") (pinfunction "VDD33_C27") (pintype "power_in"))
      (node (ref "SENSOR") (pin "D26") (pinfunction "VDD33_D26") (pintype "power_in"))
      (node (ref "SENSOR") (pin "D3") (pinfunction "VDD33_D3") (pintype "power_in"))
      (node (ref "SENSOR") (pin "E26") (pinfunction "VDD33_E26") (pintype "power_in"))
      (node (ref "SENSOR") (pin "F26") (pinfunction "VDD33_F26") (pintype "power_in"))
      (node (ref "SENSOR") (pin "F5") (pinfunction "VDD33_F5") (pintype "power_in"))
      (node (ref "TP7") (pin "TP") (pinfunction "TP_TP") (pintype "input"))
      (node (ref "U4") (pin "13") (pinfunction "VCCB_13") (pintype "power_in"))
      (node (ref "U5") (pin "13") (pinfunction "VCCB_13") (pintype "power_in"))
      (node (ref "U6") (pin "13") (pinfunction "VCCB_13") (pintype "power_in"))
      (node (ref "X-NORTH") (pin "109") (pinfunction "109_109") (pintype "bidirectional"))
      (node (ref "X-NORTH") (pin "115") (pinfunction "115_115") (pintype "bidirectional"))
      (node (ref "X-NORTH") (pin "121") (pinfunction "121_121") (pintype "bidirectional"))
      (node (ref "X-NORTH") (pin "127") (pinfunction "127_127") (pintype "bidirectional"))
      (node (ref "X-NORTH") (pin "133") (pinfunction "133_133") (pintype "bidirectional"))
    )
    (net (code "98") (name "N_VE_CV") (class "Default")
      (node (ref "C10") (pin "1") (pinfunction "1_1") (pintype "passive"))
      (node (ref "R7") (pin "1") (pinfunction "1_1") (pintype "passive"))
      (node (ref "X-NORTH") (pin "6") (pinfunction "6_6") (pintype "bidirectional"))
    )
    (net (code "99") (name "N_VE_OV") (class "Default")
      (node (ref "UNE") (pin "7") (pinfunction "OUTB_7") (pintype "output"))
      (node (ref "X-NORTH") (pin "5") (pinfunction "5_5") (pintype "bidirectional"))
    )
    (net (code "100") (name "N_VE_UV") (class "Default")
      (node (ref "UNE") (pin "1") (pinfunction "OUTA_1") (pintype "output"))
      (node (ref "X-NORTH") (pin "11") (pinfunction "11_11") (pintype "bidirectional"))
    )
    (net (code "101") (name "N_VN") (class "Default")
      (node (ref "C31") (pin "1") (pinfunction "1_1") (pintype "passive"))
      (node (ref "C32") (pin "1") (pinfunction "1_1") (pintype "passive"))
      (node (ref "C33") (pin "1") (pinfunction "1_1") (pintype "passive"))
      (node (ref "C34") (pin "1") (pinfunction "1_1") (pintype "passive"))
      (node (ref "C35") (pin "1") (pinfunction "1_1") (pintype "passive"))
      (node (ref "C36") (pin "1") (pinfunction "1_1") (pintype "passive"))
      (node (ref "C37") (pin "1") (pinfunction "1_1") (pintype "passive"))
      (node (ref "C38") (pin "1") (pinfunction "1_1") (pintype "passive"))
      (node (ref "C39") (pin "1") (pinfunction "1_1") (pintype "passive"))
      (node (ref "C40") (pin "1") (pinfunction "1_1") (pintype "passive"))
      (node (ref "C41") (pin "1") (pinfunction "1_1") (pintype "passive"))
      (node (ref "C42") (pin "1") (pinfunction "1_1") (pintype "passive"))
      (node (ref "C43") (pin "1") (pinfunction "1_1") (pintype "passive"))
      (node (ref "C44") (pin "1") (pinfunction "1_1") (pintype "passive"))
      (node (ref "C68") (pin "1") (pinfunction "1_1") (pintype "passive"))
      (node (ref "C70") (pin "1") (pinfunction "1_1") (pintype "passive"))
      (node (ref "C78") (pin "1") (pinfunction "1_1") (pintype "passive"))
      (node (ref "C79") (pin "1") (pinfunction "1_1") (pintype "passive"))
      (node (ref "C80") (pin "1") (pinfunction "1_1") (pintype "passive"))
      (node (ref "C87") (pin "1") (pinfunction "1_1") (pintype "passive"))
      (node (ref "C88") (pin "1") (pinfunction "1_1") (pintype "passive"))
      (node (ref "C89") (pin "1") (pinfunction "1_1") (pintype "passive"))
      (node (ref "SENSOR") (pin "A10") (pinfunction "VDD18_A10") (pintype "power_in"))
      (node (ref "SENSOR") (pin "A15") (pinfunction "VDD18_A15") (pintype "power_in"))
      (node (ref "SENSOR") (pin "A16") (pinfunction "VDD18_A16") (pintype "power_in"))
      (node (ref "SENSOR") (pin "A22") (pinfunction "VDD18_A22") (pintype "power_in"))
      (node (ref "SENSOR") (pin "A26") (pinfunction "VDD18_A26") (pintype "power_in"))
      (node (ref "SENSOR") (pin "A27") (pinfunction "VDD18_A27") (pintype "power_in"))
      (node (ref "SENSOR") (pin "B4") (pinfunction "VDD18_B4") (pintype "power_in"))
      (node (ref "SENSOR") (pin "E1") (pinfunction "VDD18_PLL_E1") (pintype "power_in"))
      (node (ref "SENSOR") (pin "H10") (pinfunction "VDD18_H10") (pintype "power_in"))
      (node (ref "SENSOR") (pin "H15") (pinfunction "VDD18_H15") (pintype "power_in"))
      (node (ref "SENSOR") (pin "H16") (pinfunction "VDD18_H16") (pintype "power_in"))
      (node (ref "SENSOR") (pin "H22") (pinfunction "VDD18_H22") (pintype "power_in"))
      (node (ref "SENSOR") (pin "H26") (pinfunction "VDD18_H26") (pintype "power_in"))
      (node (ref "SENSOR") (pin "H5") (pinfunction "VDD18_H5") (pintype "power_in"))
      (node (ref "TP5") (pin "TP") (pinfunction "TP_TP") (pintype "input"))
      (node (ref "U5") (pin "14") (pinfunction "VCCA_14") (pintype "power_in"))
      (node (ref "U5") (pin "15") (pinfunction "DIR1_15") (pintype "input"))
      (node (ref "U5") (pin "16") (pinfunction "DIR2_16") (pintype "input"))
      (node (ref "U5") (pin "5") (pinfunction "DIR3_5") (pintype "input"))
      (node (ref "U6") (pin "14") (pinfunction "VCCA_14") (pintype "power_in"))
      (node (ref "U6") (pin "15") (pinfunction "DIR1_15") (pintype "input"))
      (node (ref "U6") (pin "5") (pinfunction "DIR3_5") (pintype "input"))
      (node (ref "U6") (pin "6") (pinfunction "DIR4_6") (pintype "input"))
      (node (ref "X-NORTH") (pin "49") (pinfunction "49_49") (pintype "bidirectional"))
      (node (ref "X-NORTH") (pin "55") (pinfunction "55_55") (pintype "bidirectional"))
      (node (ref "X-NORTH") (pin "61") (pinfunction "61_61") (pintype "bidirectional"))
      (node (ref "X-NORTH") (pin "67") (pinfunction "67_67") (pintype "bidirectional"))
      (node (ref "X-NORTH") (pin "73") (pinfunction "73_73") (pintype "bidirectional"))
      (node (ref "X-NORTH") (pin "79") (pinfunction "79_79") (pintype "bidirectional"))
      (node (ref "X-NORTH") (pin "85") (pinfunction "85_85") (pintype "bidirectional"))
      (node (ref "X-NORTH") (pin "91") (pinfunction "91_91") (pintype "bidirectional"))
      (node (ref "X-NORTH") (pin "97") (pinfunction "97_97") (pintype "bidirectional"))
    )
    (net (code "102") (name "N_VN_CV") (class "Default")
      (node (ref "C9") (pin "1") (pinfunction "1_1") (pintype "passive"))
      (node (ref "R4") (pin "1") (pinfunction "1_1") (pintype "passive"))
      (node (ref "X-NORTH") (pin "4") (pinfunction "4_4") (pintype "bidirectional"))
    )
    (net (code "103") (name "N_VN_OV") (class "Default")
      (node (ref "UNN") (pin "7") (pinfunction "OUTB_7") (pintype "output"))
      (node (ref "X-NORTH") (pin "3") (pinfunction "3_3") (pintype "bidirectional"))
    )
    (net (code "104") (name "N_VN_UV") (class "Default")
      (node (ref "UNN") (pin "1") (pinfunction "OUTA_1") (pintype "output"))
      (node (ref "X-NORTH") (pin "9") (pinfunction "9_9") (pintype "bidirectional"))
    )
    (net (code "105") (name "N_VW") (class "Default")
      (node (ref "C57") (pin "1") (pinfunction "1_1") (pintype "passive"))
      (node (ref "C58") (pin "1") (pinfunction "1_1") (pintype "passive"))
      (node (ref "C92") (pin "1") (pinfunction "1_1") (pintype "passive"))
      (node (ref "SENSOR") (pin "E2") (pinfunction "VDD_RES_E2") (pintype "power_in"))
      (node (ref "SENSOR") (pin "G4") (pinfunction "VDD_RES_G4") (pintype "power_in"))
      (node (ref "TP8") (pin "TP") (pinfunction "TP_TP") (pintype "input"))
      (node (ref "X-NORTH") (pin "13") (pinfunction "13_13") (pintype "bidirectional"))
      (node (ref "X-NORTH") (pin "19") (pinfunction "19_19") (pintype "bidirectional"))
      (node (ref "X-NORTH") (pin "25") (pinfunction "25_25") (pintype "bidirectional"))
      (node (ref "X-NORTH") (pin "31") (pinfunction "31_31") (pintype "bidirectional"))
      (node (ref "X-NORTH") (pin "37") (pinfunction "37_37") (pintype "bidirectional"))
    )
    (net (code "106") (name "N_VW_CV") (class "Default")
      (node (ref "C8") (pin "1") (pinfunction "1_1") (pintype "passive"))
      (node (ref "R1") (pin "1") (pinfunction "1_1") (pintype "passive"))
      (node (ref "X-NORTH") (pin "2") (pinfunction "2_2") (pintype "bidirectional"))
    )
    (net (code "107") (name "N_VW_OV") (class "Default")
      (node (ref "UNW") (pin "7") (pinfunction "OUTB_7") (pintype "output"))
      (node (ref "X-NORTH") (pin "1") (pinfunction "1_1") (pintype "bidirectional"))
    )
    (net (code "108") (name "N_VW_UV") (class "Default")
      (node (ref "UNW") (pin "1") (pinfunction "OUTA_1") (pintype "output"))
      (node (ref "X-NORTH") (pin "7") (pinfunction "7_7") (pintype "bidirectional"))
    )
    (net (code "109") (name "Net-(SENSORB-CMDN)") (class "Default")
      (node (ref "C61") (pin "1") (pinfunction "1_1") (pintype "passive"))
      (node (ref "SENSOR") (pin "F1") (pinfunction "CMDN_F1") (pintype "bidirectional"))
    )
    (net (code "110") (name "Net-(SENSORB-CMDP)") (class "Default")
      (node (ref "C22") (pin "2") (pinfunction "2_2") (pintype "passive"))
      (node (ref "SENSOR") (pin "F2") (pinfunction "CMDP_F2") (pintype "bidirectional"))
    )
    (net (code "111") (name "Net-(SENSORB-CMDP_COMP)") (class "Default")
      (node (ref "C28") (pin "2") (pinfunction "2_2") (pintype "passive"))
      (node (ref "SENSOR") (pin "H3") (pinfunction "CMDP_COMP_H3") (pintype "bidirectional"))
    )
    (net (code "112") (name "Net-(SENSORB-CMDP_COMP_INV)") (class "Default")
      (node (ref "C27") (pin "2") (pinfunction "2_2") (pintype "passive"))
      (node (ref "SENSOR") (pin "F3") (pinfunction "CMDP_COMP_INV_F3") (pintype "bidirectional"))
    )
    (net (code "113") (name "Net-(SENSORB-CMD_COLAMP)") (class "Default")
      (node (ref "C25") (pin "2") (pinfunction "2_2") (pintype "passive"))
      (node (ref "SENSOR") (pin "C6") (pinfunction "CMD_COLAMP_C6") (pintype "bidirectional"))
    )
    (net (code "114") (name "Net-(SENSORB-CMD_COL_LOAD)") (class "Default")
      (node (ref "C23") (pin "2") (pinfunction "2_2") (pintype "passive"))
      (node (ref "SENSOR") (pin "B1") (pinfunction "CMD_COL_LOAD_B1") (pintype "bidirectional"))
    )
    (net (code "115") (name "Net-(SENSORB-CMD_COL_PC)") (class "Default")
      (node (ref "C26") (pin "2") (pinfunction "2_2") (pintype "passive"))
      (node (ref "SENSOR") (pin "D1") (pinfunction "CMD_COL_PC_D1") (pintype "bidirectional"))
    )
    (net (code "116") (name "Net-(SENSORB-CMD_LVDS)") (class "Default")
      (node (ref "C62") (pin "1") (pinfunction "1_1") (pintype "passive"))
      (node (ref "SENSOR") (pin "C1") (pinfunction "CMD_LVDS_C1") (pintype "bidirectional"))
    )
    (net (code "117") (name "Net-(SENSORB-CMD_RAMP)") (class "Default")
      (node (ref "C24") (pin "2") (pinfunction "2_2") (pintype "passive"))
      (node (ref "SENSOR") (pin "B29") (pinfunction "CMD_RAMP_B29") (pintype "bidirectional"))
    )
    (net (code "118") (name "Net-(SENSORB-VBGAP)") (class "Default")
      (node (ref "C64") (pin "1") (pinfunction "1_1") (pintype "passive"))
      (node (ref "SENSOR") (pin "C29") (pinfunction "VBGAP_C29") (pintype "bidirectional"))
    )
    (net (code "119") (name "Net-(SENSORB-VCLAMP)") (class "Default")
      (node (ref "C63") (pin "1") (pinfunction "1_1") (pintype "passive"))
      (node (ref "SENSOR") (pin "D4") (pinfunction "VCLAMP_D4") (pintype "bidirectional"))
    )
    (net (code "120") (name "Net-(SENSORB-VCLAMP_ADC)") (class "Default")
      (node (ref "C60") (pin "1") (pinfunction "1_1") (pintype "passive"))
      (node (ref "SENSOR") (pin "G2") (pinfunction "VCLAMP_ADC_G2") (pintype "bidirectional"))
    )
    (net (code "121") (name "Net-(SENSORB-VPCH_H)") (class "Default")
      (node (ref "C71") (pin "1") (pinfunction "1_1") (pintype "passive"))
      (node (ref "SENSOR") (pin "C4") (pinfunction "VPCH_H_C4") (pintype "bidirectional"))
    )
    (net (code "122") (name "Net-(SENSORB-VPCH_L)") (class "Default")
      (node (ref "C14") (pin "1") (pinfunction "1_1") (pintype "passive"))
      (node (ref "SENSOR") (pin "A4") (pinfunction "VPCH_L_A4") (pintype "bidirectional"))
    )
    (net (code "123") (name "Net-(SENSORB-VREF)") (class "Default")
      (node (ref "C29") (pin "1") (pinfunction "1_1") (pintype "passive"))
      (node (ref "SENSOR") (pin "A3") (pinfunction "VREF_A3") (pintype "bidirectional"))
    )
    (net (code "124") (name "Net-(SENSORB-VREF_ADC)") (class "Default")
      (node (ref "C30") (pin "1") (pinfunction "1_1") (pintype "passive"))
      (node (ref "SENSOR") (pin "B3") (pinfunction "VREF_ADC_B3") (pintype "bidirectional"))
    )
    (net (code "125") (name "Net-(SENSORB-VRES_L)") (class "Default")
      (node (ref "C15") (pin "1") (pinfunction "1_1") (pintype "passive"))
      (node (ref "SENSOR") (pin "D5") (pinfunction "VRES_L_D5") (pintype "bidirectional"))
    )
    (net (code "126") (name "Net-(SENSORB-VTF_LOW0)") (class "Default")
      (node (ref "C18") (pin "1") (pinfunction "1_1") (pintype "passive"))
      (node (ref "SENSOR") (pin "C5") (pinfunction "VTF_LOW0_C5") (pintype "bidirectional"))
    )
    (net (code "127") (name "Net-(SENSORB-VTF_LOW1)") (class "Default")
      (node (ref "C19") (pin "1") (pinfunction "1_1") (pintype "passive"))
      (node (ref "SENSOR") (pin "D6") (pinfunction "VTF_LOW1_D6") (pintype "bidirectional"))
    )
    (net (code "128") (name "Net-(SENSORB-VTF_LOW2)") (class "Default")
      (node (ref "C20") (pin "1") (pinfunction "1_1") (pintype "passive"))
      (node (ref "SENSOR") (pin "B30") (pinfunction "VTF_LOW2_B30") (pintype "bidirectional"))
    )
    (net (code "129") (name "Net-(SENSORB-VTF_LOW3)") (class "Default")
      (node (ref "C21") (pin "1") (pinfunction "1_1") (pintype "passive"))
      (node (ref "SENSOR") (pin "C30") (pinfunction "VTF_LOW3_C30") (pintype "bidirectional"))
    )
    (net (code "130") (name "Net-(U3-ADJ)") (class "Default")
      (node (ref "R21") (pin "1") (pinfunction "1_1") (pintype "passive"))
      (node (ref "R22") (pin "2") (pinfunction "2_2") (pintype "passive"))
      (node (ref "U3") (pin "5") (pinfunction "ADJ_5") (pintype "input"))
    )
    (net (code "131") (name "Net-(U6-B4)") (class "Default")
      (node (ref "TP9") (pin "TP") (pinfunction "TP_TP") (pintype "input"))
      (node (ref "U6") (pin "9") (pinfunction "B4_9") (pintype "bidirectional"))
    )
    (net (code "132") (name "Net-(UEP-WP)") (class "Default")
      (node (ref "R1X") (pin "2") (pinfunction "2_2") (pintype "passive"))
      (node (ref "R2X") (pin "1") (pinfunction "1_1") (pintype "passive"))
      (node (ref "UEP") (pin "7") (pinfunction "WP_7") (pintype "input"))
    )
    (net (code "133") (name "Net-(UNE-VINA+)") (class "Default")
      (node (ref "R7") (pin "2") (pinfunction "2_2") (pintype "passive"))
      (node (ref "R8") (pin "1") (pinfunction "1_1") (pintype "passive"))
      (node (ref "UNE") (pin "3") (pinfunction "VINA+_3") (pintype "input"))
    )
    (net (code "134") (name "Net-(UNE-VINB-)") (class "Default")
      (node (ref "R8") (pin "2") (pinfunction "2_2") (pintype "passive"))
      (node (ref "R9") (pin "1") (pinfunction "1_1") (pintype "passive"))
      (node (ref "UNE") (pin "6") (pinfunction "VINB-_6") (pintype "input"))
    )
    (net (code "135") (name "Net-(UNN-VINA+)") (class "Default")
      (node (ref "R4") (pin "2") (pinfunction "2_2") (pintype "passive"))
      (node (ref "R5") (pin "1") (pinfunction "1_1") (pintype "passive"))
      (node (ref "UNN") (pin "3") (pinfunction "VINA+_3") (pintype "input"))
    )
    (net (code "136") (name "Net-(UNN-VINB-)") (class "Default")
      (node (ref "R5") (pin "2") (pinfunction "2_2") (pintype "passive"))
      (node (ref "R6") (pin "1") (pinfunction "1_1") (pintype "passive"))
      (node (ref "UNN") (pin "6") (pinfunction "VINB-_6") (pintype "input"))
    )
    (net (code "137") (name "Net-(UNW-VINA+)") (class "Default")
      (node (ref "R1") (pin "2") (pinfunction "2_2") (pintype "passive"))
      (node (ref "R2") (pin "1") (pinfunction "1_1") (pintype "passive"))
      (node (ref "UNW") (pin "3") (pinfunction "VINA+_3") (pintype "input"))
    )
    (net (code "138") (name "Net-(UNW-VINB-)") (class "Default")
      (node (ref "R2") (pin "2") (pinfunction "2_2") (pintype "passive"))
      (node (ref "R3") (pin "1") (pinfunction "1_1") (pintype "passive"))
      (node (ref "UNW") (pin "6") (pinfunction "VINB-_6") (pintype "input"))
    )
    (net (code "139") (name "Net-(USE-VINA+)") (class "Default")
      (node (ref "R10") (pin "2") (pinfunction "2_2") (pintype "passive"))
      (node (ref "R11") (pin "1") (pinfunction "1_1") (pintype "passive"))
      (node (ref "USE") (pin "3") (pinfunction "VINA+_3") (pintype "input"))
    )
    (net (code "140") (name "Net-(USE-VINB-)") (class "Default")
      (node (ref "R11") (pin "2") (pinfunction "2_2") (pintype "passive"))
      (node (ref "R12") (pin "1") (pinfunction "1_1") (pintype "passive"))
      (node (ref "USE") (pin "6") (pinfunction "VINB-_6") (pintype "input"))
    )
    (net (code "141") (name "Net-(USS-VINA+)") (class "Default")
      (node (ref "R13") (pin "2") (pinfunction "2_2") (pintype "passive"))
      (node (ref "R14") (pin "1") (pinfunction "1_1") (pintype "passive"))
      (node (ref "USS") (pin "3") (pinfunction "VINA+_3") (pintype "input"))
    )
    (net (code "142") (name "Net-(USS-VINB-)") (class "Default")
      (node (ref "R14") (pin "2") (pinfunction "2_2") (pintype "passive"))
      (node (ref "R15") (pin "1") (pinfunction "1_1") (pintype "passive"))
      (node (ref "USS") (pin "6") (pinfunction "VINB-_6") (pintype "input"))
    )
    (net (code "143") (name "Net-(USW-VINA+)") (class "Default")
      (node (ref "R16") (pin "2") (pinfunction "2_2") (pintype "passive"))
      (node (ref "R17") (pin "1") (pinfunction "1_1") (pintype "passive"))
      (node (ref "USW") (pin "3") (pinfunction "VINA+_3") (pintype "input"))
    )
    (net (code "144") (name "Net-(USW-VINB-)") (class "Default")
      (node (ref "R17") (pin "2") (pinfunction "2_2") (pintype "passive"))
      (node (ref "R18") (pin "1") (pinfunction "1_1") (pintype "passive"))
      (node (ref "USW") (pin "6") (pinfunction "VINB-_6") (pintype "input"))
    )
    (net (code "145") (name "S00_N") (class "Default")
      (node (ref "X-SOUTH") (pin "16") (pinfunction "16_16") (pintype "bidirectional"))
    )
    (net (code "146") (name "S00_P") (class "Default")
      (node (ref "X-SOUTH") (pin "14") (pinfunction "14_14") (pintype "bidirectional"))
    )
    (net (code "147") (name "S01_N") (class "Default")
      (node (ref "X-SOUTH") (pin "17") (pinfunction "17_17") (pintype "bidirectional"))
    )
    (net (code "148") (name "S01_P") (class "Default")
      (node (ref "X-SOUTH") (pin "15") (pinfunction "15_15") (pintype "bidirectional"))
    )
    (net (code "149") (name "S02_N") (class "Default")
      (node (ref "X-SOUTH") (pin "22") (pinfunction "22_22") (pintype "bidirectional"))
    )
    (net (code "150") (name "S02_P") (class "Default")
      (node (ref "X-SOUTH") (pin "20") (pinfunction "20_20") (pintype "bidirectional"))
    )
    (net (code "151") (name "S03_N") (class "Default")
      (node (ref "X-SOUTH") (pin "23") (pinfunction "23_23") (pintype "bidirectional"))
    )
    (net (code "152") (name "S03_P") (class "Default")
      (node (ref "X-SOUTH") (pin "21") (pinfunction "21_21") (pintype "bidirectional"))
    )
    (net (code "153") (name "S04_N") (class "Default")
      (node (ref "SENSOR") (pin "C24") (pinfunction "OUT32_N_C24") (pintype "output"))
      (node (ref "X-SOUTH") (pin "28") (pinfunction "28_28") (pintype "bidirectional"))
    )
    (net (code "154") (name "S04_P") (class "Default")
      (node (ref "SENSOR") (pin "C25") (pinfunction "OUT32_P_C25") (pintype "output"))
      (node (ref "X-SOUTH") (pin "26") (pinfunction "26_26") (pintype "bidirectional"))
    )
    (net (code "155") (name "S05_N") (class "Default")
      (node (ref "X-SOUTH") (pin "29") (pinfunction "29_29") (pintype "bidirectional"))
    )
    (net (code "156") (name "S05_P") (class "Default")
      (node (ref "X-SOUTH") (pin "27") (pinfunction "27_27") (pintype "bidirectional"))
    )
    (net (code "157") (name "S06_N") (class "Default")
      (node (ref "SENSOR") (pin "D23") (pinfunction "OUT30_N_D23") (pintype "output"))
      (node (ref "X-SOUTH") (pin "34") (pinfunction "34_34") (pintype "bidirectional"))
    )
    (net (code "158") (name "S06_P") (class "Default")
      (node (ref "SENSOR") (pin "D24") (pinfunction "OUT30_P_D24") (pintype "output"))
      (node (ref "X-SOUTH") (pin "32") (pinfunction "32_32") (pintype "bidirectional"))
    )
    (net (code "159") (name "S07_N") (class "Default")
      (node (ref "SENSOR") (pin "B24") (pinfunction "OUT31_N_B24") (pintype "output"))
      (node (ref "X-SOUTH") (pin "35") (pinfunction "35_35") (pintype "bidirectional"))
    )
    (net (code "160") (name "S07_P") (class "Default")
      (node (ref "SENSOR") (pin "B25") (pinfunction "OUT31_P_B25") (pintype "output"))
      (node (ref "X-SOUTH") (pin "33") (pinfunction "33_33") (pintype "bidirectional"))
    )
    (net (code "161") (name "S08_N") (class "Default")
      (node (ref "SENSOR") (pin "D21") (pinfunction "OUT27_N_D21") (pintype "output"))
      (node (ref "X-SOUTH") (pin "40") (pinfunction "40_40") (pintype "bidirectional"))
    )
    (net (code "162") (name "S08_P") (class "Default")
      (node (ref "SENSOR") (pin "D22") (pinfunction "OUT27_P_D22") (pintype "output"))
      (node (ref "X-SOUTH") (pin "38") (pinfunction "38_38") (pintype "bidirectional"))
    )
    (net (code "163") (name "S09_N") (class "Default")
      (node (ref "SENSOR") (pin "A23") (pinfunction "OUT29_N_A23") (pintype "output"))
      (node (ref "X-SOUTH") (pin "41") (pinfunction "41_41") (pintype "bidirectional"))
    )
    (net (code "164") (name "S09_P") (class "Default")
      (node (ref "SENSOR") (pin "A24") (pinfunction "OUT29_P_A24") (pintype "output"))
      (node (ref "X-SOUTH") (pin "39") (pinfunction "39_39") (pintype "bidirectional"))
    )
    (net (code "165") (name "S10_N") (class "Default")
      (node (ref "SENSOR") (pin "C21") (pinfunction "OUT28_N_C21") (pintype "output"))
      (node (ref "X-SOUTH") (pin "46") (pinfunction "46_46") (pintype "bidirectional"))
    )
    (net (code "166") (name "S10_P") (class "Default")
      (node (ref "SENSOR") (pin "C22") (pinfunction "OUT28_P_C22") (pintype "output"))
      (node (ref "X-SOUTH") (pin "44") (pinfunction "44_44") (pintype "bidirectional"))
    )
    (net (code "167") (name "S11_N") (class "Default")
      (node (ref "SENSOR") (pin "B20") (pinfunction "OUT26_N_B20") (pintype "output"))
      (node (ref "X-SOUTH") (pin "47") (pinfunction "47_47") (pintype "bidirectional"))
    )
    (net (code "168") (name "S11_P") (class "Default")
      (node (ref "SENSOR") (pin "B21") (pinfunction "OUT26_P_B21") (pintype "output"))
      (node (ref "X-SOUTH") (pin "45") (pinfunction "45_45") (pintype "bidirectional"))
    )
    (net (code "169") (name "S12_N") (class "Default")
      (node (ref "SENSOR") (pin "D19") (pinfunction "OUT24_N_D19") (pintype "output"))
      (node (ref "X-SOUTH") (pin "52") (pinfunction "52_52") (pintype "bidirectional"))
    )
    (net (code "170") (name "S12_P") (class "Default")
      (node (ref "SENSOR") (pin "D20") (pinfunction "OUT24_P_D20") (pintype "output"))
      (node (ref "X-SOUTH") (pin "50") (pinfunction "50_50") (pintype "bidirectional"))
    )
    (net (code "171") (name "S13_N") (class "Default")
      (node (ref "SENSOR") (pin "A19") (pinfunction "OUT23_N_A19") (pintype "output"))
      (node (ref "X-SOUTH") (pin "53") (pinfunction "53_53") (pintype "bidirectional"))
    )
    (net (code "172") (name "S13_P") (class "Default")
      (node (ref "SENSOR") (pin "A20") (pinfunction "OUT23_P_A20") (pintype "output"))
      (node (ref "X-SOUTH") (pin "51") (pinfunction "51_51") (pintype "bidirectional"))
    )
    (net (code "173") (name "S14_N") (class "Default")
      (node (ref "SENSOR") (pin "C19") (pinfunction "OUT25_N_C19") (pintype "output"))
      (node (ref "X-SOUTH") (pin "58") (pinfunction "58_58") (pintype "bidirectional"))
    )
    (net (code "174") (name "S14_P") (class "Default")
      (node (ref "SENSOR") (pin "C20") (pinfunction "OUT25_P_C20") (pintype "output"))
      (node (ref "X-SOUTH") (pin "56") (pinfunction "56_56") (pintype "bidirectional"))
    )
    (net (code "175") (name "S15_N") (class "Default")
      (node (ref "SENSOR") (pin "B18") (pinfunction "OUT22_N_B18") (pintype "output"))
      (node (ref "X-SOUTH") (pin "59") (pinfunction "59_59") (pintype "bidirectional"))
    )
    (net (code "176") (name "S15_P") (class "Default")
      (node (ref "SENSOR") (pin "B19") (pinfunction "OUT22_P_B19") (pintype "output"))
      (node (ref "X-SOUTH") (pin "57") (pinfunction "57_57") (pintype "bidirectional"))
    )
    (net (code "177") (name "S16_N") (class "Default")
      (node (ref "SENSOR") (pin "C17") (pinfunction "OUT21_N_C17") (pintype "output"))
      (node (ref "X-SOUTH") (pin "64") (pinfunction "64_64") (pintype "bidirectional"))
    )
    (net (code "178") (name "S16_P") (class "Default")
      (node (ref "SENSOR") (pin "C18") (pinfunction "OUT21_P_C18") (pintype "output"))
      (node (ref "X-SOUTH") (pin "62") (pinfunction "62_62") (pintype "bidirectional"))
    )
    (net (code "179") (name "S17_N") (class "Default")
      (node (ref "SENSOR") (pin "A17") (pinfunction "OUT19_N_A17") (pintype "output"))
      (node (ref "X-SOUTH") (pin "65") (pinfunction "65_65") (pintype "bidirectional"))
    )
    (net (code "180") (name "S17_P") (class "Default")
      (node (ref "SENSOR") (pin "A18") (pinfunction "OUT19_P_A18") (pintype "output"))
      (node (ref "X-SOUTH") (pin "63") (pinfunction "63_63") (pintype "bidirectional"))
    )
    (net (code "181") (name "S18_N") (class "Default")
      (node (ref "SENSOR") (pin "D17") (pinfunction "OUT20_N_D17") (pintype "output"))
      (node (ref "X-SOUTH") (pin "70") (pinfunction "70_70") (pintype "bidirectional"))
    )
    (net (code "182") (name "S18_P") (class "Default")
      (node (ref "SENSOR") (pin "D18") (pinfunction "OUT20_P_D18") (pintype "output"))
      (node (ref "X-SOUTH") (pin "68") (pinfunction "68_68") (pintype "bidirectional"))
    )
    (net (code "183") (name "S19_N") (class "Default")
      (node (ref "SENSOR") (pin "B16") (pinfunction "OUT18_N_B16") (pintype "output"))
      (node (ref "X-SOUTH") (pin "71") (pinfunction "71_71") (pintype "bidirectional"))
    )
    (net (code "184") (name "S19_P") (class "Default")
      (node (ref "SENSOR") (pin "B17") (pinfunction "OUT18_P_B17") (pintype "output"))
      (node (ref "X-SOUTH") (pin "69") (pinfunction "69_69") (pintype "bidirectional"))
    )
    (net (code "185") (name "S20_N") (class "Default")
      (node (ref "SENSOR") (pin "D15") (pinfunction "OUT17_N_D15") (pintype "output"))
      (node (ref "X-SOUTH") (pin "76") (pinfunction "76_76") (pintype "bidirectional"))
    )
    (net (code "186") (name "S20_P") (class "Default")
      (node (ref "SENSOR") (pin "D16") (pinfunction "OUT17_P_D16") (pintype "output"))
      (node (ref "X-SOUTH") (pin "74") (pinfunction "74_74") (pintype "bidirectional"))
    )
    (net (code "187") (name "S21_N") (class "Default")
      (node (ref "SENSOR") (pin "B14") (pinfunction "OUT16_N_B14") (pintype "output"))
      (node (ref "X-SOUTH") (pin "77") (pinfunction "77_77") (pintype "bidirectional"))
    )
    (net (code "188") (name "S21_P") (class "Default")
      (node (ref "SENSOR") (pin "B15") (pinfunction "OUT16_P_B15") (pintype "output"))
      (node (ref "X-SOUTH") (pin "75") (pinfunction "75_75") (pintype "bidirectional"))
    )
    (net (code "189") (name "S22_N") (class "Default")
      (node (ref "SENSOR") (pin "D13") (pinfunction "OUT15_N_D13") (pintype "output"))
      (node (ref "X-SOUTH") (pin "82") (pinfunction "82_82") (pintype "bidirectional"))
    )
    (net (code "190") (name "S22_P") (class "Default")
      (node (ref "SENSOR") (pin "D14") (pinfunction "OUT15_P_D14") (pintype "output"))
      (node (ref "X-SOUTH") (pin "80") (pinfunction "80_80") (pintype "bidirectional"))
    )
    (net (code "191") (name "S23_N") (class "Default")
      (node (ref "SENSOR") (pin "A13") (pinfunction "OUT13_N_A13") (pintype "output"))
      (node (ref "X-SOUTH") (pin "83") (pinfunction "83_83") (pintype "bidirectional"))
    )
    (net (code "192") (name "S23_P") (class "Default")
      (node (ref "SENSOR") (pin "A14") (pinfunction "OUT13_P_A14") (pintype "output"))
      (node (ref "X-SOUTH") (pin "81") (pinfunction "81_81") (pintype "bidirectional"))
    )
    (net (code "193") (name "S24_N") (class "Default")
      (node (ref "SENSOR") (pin "C13") (pinfunction "OUT14_N_C13") (pintype "output"))
      (node (ref "X-SOUTH") (pin "88") (pinfunction "88_88") (pintype "bidirectional"))
    )
    (net (code "194") (name "S24_P") (class "Default")
      (node (ref "SENSOR") (pin "C14") (pinfunction "OUT14_P_C14") (pintype "output"))
      (node (ref "X-SOUTH") (pin "86") (pinfunction "86_86") (pintype "bidirectional"))
    )
    (net (code "195") (name "S25_N") (class "Default")
      (node (ref "SENSOR") (pin "B12") (pinfunction "OUT12_N_B12") (pintype "output"))
      (node (ref "X-SOUTH") (pin "89") (pinfunction "89_89") (pintype "bidirectional"))
    )
    (net (code "196") (name "S25_P") (class "Default")
      (node (ref "SENSOR") (pin "B13") (pinfunction "OUT12_P_B13") (pintype "output"))
      (node (ref "X-SOUTH") (pin "87") (pinfunction "87_87") (pintype "bidirectional"))
    )
    (net (code "197") (name "S26_N") (class "Default")
      (node (ref "SENSOR") (pin "D11") (pinfunction "OUT10_N_D11") (pintype "output"))
      (node (ref "X-SOUTH") (pin "94") (pinfunction "94_94") (pintype "bidirectional"))
    )
    (net (code "198") (name "S26_P") (class "Default")
      (node (ref "SENSOR") (pin "D12") (pinfunction "OUT10_P_D12") (pintype "output"))
      (node (ref "X-SOUTH") (pin "92") (pinfunction "92_92") (pintype "bidirectional"))
    )
    (net (code "199") (name "S27_N") (class "Default")
      (node (ref "SENSOR") (pin "A11") (pinfunction "OUT9_N_A11") (pintype "output"))
      (node (ref "X-SOUTH") (pin "95") (pinfunction "95_95") (pintype "bidirectional"))
    )
    (net (code "200") (name "S27_P") (class "Default")
      (node (ref "SENSOR") (pin "A12") (pinfunction "OUT9_P_A12") (pintype "output"))
      (node (ref "X-SOUTH") (pin "93") (pinfunction "93_93") (pintype "bidirectional"))
    )
    (net (code "201") (name "S28_N") (class "Default")
      (node (ref "SENSOR") (pin "C11") (pinfunction "OUT11_N_C11") (pintype "output"))
      (node (ref "X-SOUTH") (pin "100") (pinfunction "100_100") (pintype "bidirectional"))
    )
    (net (code "202") (name "S28_P") (class "Default")
      (node (ref "SENSOR") (pin "C12") (pinfunction "OUT11_P_C12") (pintype "output"))
      (node (ref "X-SOUTH") (pin "98") (pinfunction "98_98") (pintype "bidirectional"))
    )
    (net (code "203") (name "S29_N") (class "Default")
      (node (ref "SENSOR") (pin "B10") (pinfunction "OUT8_N_B10") (pintype "output"))
      (node (ref "X-SOUTH") (pin "101") (pinfunction "101_101") (pintype "bidirectional"))
    )
    (net (code "204") (name "S29_P") (class "Default")
      (node (ref "SENSOR") (pin "B11") (pinfunction "OUT8_P_B11") (pintype "output"))
      (node (ref "X-SOUTH") (pin "99") (pinfunction "99_99") (pintype "bidirectional"))
    )
    (net (code "205") (name "S30_N") (class "Default")
      (node (ref "SENSOR") (pin "C9") (pinfunction "OUT7_N_C9") (pintype "output"))
      (node (ref "X-SOUTH") (pin "106") (pinfunction "106_106") (pintype "bidirectional"))
    )
    (net (code "206") (name "S30_P") (class "Default")
      (node (ref "SENSOR") (pin "C10") (pinfunction "OUT7_P_C10") (pintype "output"))
      (node (ref "X-SOUTH") (pin "104") (pinfunction "104_104") (pintype "bidirectional"))
    )
    (net (code "207") (name "S31_N") (class "Default")
      (node (ref "SENSOR") (pin "B8") (pinfunction "OUT5_N_B8") (pintype "output"))
      (node (ref "X-SOUTH") (pin "107") (pinfunction "107_107") (pintype "bidirectional"))
    )
    (net (code "208") (name "S31_P") (class "Default")
      (node (ref "SENSOR") (pin "B9") (pinfunction "OUT5_P_B9") (pintype "output"))
      (node (ref "X-SOUTH") (pin "105") (pinfunction "105_105") (pintype "bidirectional"))
    )
    (net (code "209") (name "S32_N") (class "Default")
      (node (ref "SENSOR") (pin "D9") (pinfunction "OUT6_N_D9") (pintype "output"))
      (node (ref "X-SOUTH") (pin "112") (pinfunction "112_112") (pintype "bidirectional"))
    )
    (net (code "210") (name "S32_P") (class "Default")
      (node (ref "SENSOR") (pin "D10") (pinfunction "OUT6_P_D10") (pintype "output"))
      (node (ref "X-SOUTH") (pin "110") (pinfunction "110_110") (pintype "bidirectional"))
    )
    (net (code "211") (name "S33_N") (class "Default")
      (node (ref "SENSOR") (pin "A7") (pinfunction "OUT2_N_A7") (pintype "output"))
      (node (ref "X-SOUTH") (pin "113") (pinfunction "113_113") (pintype "bidirectional"))
    )
    (net (code "212") (name "S33_P") (class "Default")
      (node (ref "SENSOR") (pin "A8") (pinfunction "OUT2_P_A8") (pintype "output"))
      (node (ref "X-SOUTH") (pin "111") (pinfunction "111_111") (pintype "bidirectional"))
    )
    (net (code "213") (name "S34_N") (class "Default")
      (node (ref "SENSOR") (pin "C7") (pinfunction "OUT4_N_C7") (pintype "output"))
      (node (ref "X-SOUTH") (pin "118") (pinfunction "118_118") (pintype "bidirectional"))
    )
    (net (code "214") (name "S34_P") (class "Default")
      (node (ref "SENSOR") (pin "C8") (pinfunction "OUT4_P_C8") (pintype "output"))
      (node (ref "X-SOUTH") (pin "116") (pinfunction "116_116") (pintype "bidirectional"))
    )
    (net (code "215") (name "S35_N") (class "Default")
      (node (ref "SENSOR") (pin "B6") (pinfunction "OUT1_N_B6") (pintype "output"))
      (node (ref "X-SOUTH") (pin "119") (pinfunction "119_119") (pintype "bidirectional"))
    )
    (net (code "216") (name "S35_P") (class "Default")
      (node (ref "SENSOR") (pin "B7") (pinfunction "OUT1_P_B7") (pintype "output"))
      (node (ref "X-SOUTH") (pin "117") (pinfunction "117_117") (pintype "bidirectional"))
    )
    (net (code "217") (name "S36_N") (class "Default")
      (node (ref "SENSOR") (pin "D7") (pinfunction "OUT3_N_D7") (pintype "output"))
      (node (ref "X-SOUTH") (pin "124") (pinfunction "124_124") (pintype "bidirectional"))
    )
    (net (code "218") (name "S36_P") (class "Default")
      (node (ref "SENSOR") (pin "D8") (pinfunction "OUT3_P_D8") (pintype "output"))
      (node (ref "X-SOUTH") (pin "122") (pinfunction "122_122") (pintype "bidirectional"))
    )
    (net (code "219") (name "S37_N") (class "Default")
      (node (ref "SENSOR") (pin "A5") (pinfunction "OUTCTR_N_A5") (pintype "output"))
      (node (ref "X-SOUTH") (pin "125") (pinfunction "125_125") (pintype "bidirectional"))
    )
    (net (code "220") (name "S37_P") (class "Default")
      (node (ref "SENSOR") (pin "A6") (pinfunction "OUTCTR_P_A6") (pintype "output"))
      (node (ref "X-SOUTH") (pin "123") (pinfunction "123_123") (pintype "bidirectional"))
    )
    (net (code "221") (name "S38_N") (class "Default")
      (node (ref "X-SOUTH") (pin "130") (pinfunction "130_130") (pintype "bidirectional"))
    )
    (net (code "222") (name "S38_P") (class "Default")
      (node (ref "X-SOUTH") (pin "128") (pinfunction "128_128") (pintype "bidirectional"))
    )
    (net (code "223") (name "S39_N") (class "Default")
      (node (ref "U3") (pin "6") (pinfunction "EN_6") (pintype "input"))
      (node (ref "X-SOUTH") (pin "131") (pinfunction "131_131") (pintype "bidirectional"))
    )
    (net (code "224") (name "S39_P") (class "Default")
      (node (ref "X-SOUTH") (pin "129") (pinfunction "129_129") (pintype "bidirectional"))
    )
    (net (code "225") (name "SPI_CLK") (class "Default")
      (node (ref "SENSOR") (pin "H29") (pinfunction "SPI_CLK_H29") (pintype "input"))
      (node (ref "U4") (pin "9") (pinfunction "B4_9") (pintype "bidirectional"))
    )
    (net (code "226") (name "SPI_EN") (class "Default")
      (node (ref "SENSOR") (pin "F28") (pinfunction "SPI_EN_F28") (pintype "input"))
      (node (ref "U4") (pin "12") (pinfunction "B1_12") (pintype "bidirectional"))
    )
    (net (code "227") (name "SPI_IN") (class "Default")
      (node (ref "SENSOR") (pin "E28") (pinfunction "SPI_IN_E28") (pintype "input"))
      (node (ref "U4") (pin "10") (pinfunction "B3_10") (pintype "bidirectional"))
    )
    (net (code "228") (name "SPI_OUT") (class "Default")
      (node (ref "SENSOR") (pin "G28") (pinfunction "SPI_OUT_G28") (pintype "output"))
      (node (ref "U4") (pin "11") (pinfunction "B2_11") (pintype "bidirectional"))
    )
    (net (code "229") (name "SYS_RES_N") (class "Default")
      (node (ref "SENSOR") (pin "F30") (pinfunction "SYS_RES_N_F30") (pintype "input"))
      (node (ref "U5") (pin "10") (pinfunction "B3_10") (pintype "bidirectional"))
    )
    (net (code "230") (name "S_CHK_EN") (class "Default")
      (node (ref "X-SOUTH") (pin "8") (pinfunction "8_8") (pintype "bidirectional"))
    )
    (net (code "231") (name "S_CHK_V") (class "Default")
      (node (ref "C5") (pin "1") (pinfunction "1_1") (pintype "passive"))
      (node (ref "C6") (pin "1") (pinfunction "1_1") (pintype "passive"))
      (node (ref "C7") (pin "1") (pinfunction "1_1") (pintype "passive"))
      (node (ref "R20") (pin "1") (pinfunction "1_1") (pintype "passive"))
      (node (ref "TP3") (pin "TP") (pinfunction "TP_TP") (pintype "input"))
      (node (ref "USE") (pin "8") (pinfunction "VDD_8") (pintype "power_in"))
      (node (ref "USS") (pin "8") (pinfunction "VDD_8") (pintype "power_in"))
      (node (ref "USW") (pin "8") (pinfunction "VDD_8") (pintype "power_in"))
      (node (ref "X-SOUTH") (pin "10") (pinfunction "10_10") (pintype "bidirectional"))
    )
    (net (code "232") (name "S_I2C_EN") (class "Default")
      (node (ref "X-SOUTH") (pin "137") (pinfunction "137_137") (pintype "bidirectional"))
    )
    (net (code "233") (name "S_I2C_V") (class "Default")
      (node (ref "U7") (pin "8") (pinfunction "VCC_8") (pintype "power_in"))
      (node (ref "X-SOUTH") (pin "135") (pinfunction "135_135") (pintype "bidirectional"))
    )
    (net (code "234") (name "S_REF") (class "Default")
      (node (ref "R20") (pin "2") (pinfunction "2_2") (pintype "passive"))
      (node (ref "TP4") (pin "TP") (pinfunction "TP_TP") (pintype "input"))
      (node (ref "U2") (pin "1") (pinfunction "CATHODE_1") (pintype "output"))
      (node (ref "U2") (pin "3") (pinfunction "REF_3") (pintype "input"))
      (node (ref "USE") (pin "2") (pinfunction "VINA-_2") (pintype "input"))
      (node (ref "USE") (pin "5") (pinfunction "VINB+_5") (pintype "input"))
      (node (ref "USS") (pin "2") (pinfunction "VINA-_2") (pintype "input"))
      (node (ref "USS") (pin "5") (pinfunction "VINB+_5") (pintype "input"))
      (node (ref "USW") (pin "2") (pinfunction "VINA-_2") (pintype "input"))
      (node (ref "USW") (pin "5") (pinfunction "VINB+_5") (pintype "input"))
    )
    (net (code "235") (name "S_SCK") (class "Default")
      (node (ref "X-SOUTH") (pin "144") (pinfunction "144_144") (pintype "bidirectional"))
    )
    (net (code "236") (name "S_SCL") (class "Default")
      (node (ref "U7") (pin "2") (pinfunction "SCL_2") (pintype "input"))
      (node (ref "X-SOUTH") (pin "143") (pinfunction "143_143") (pintype "bidirectional"))
    )
    (net (code "237") (name "S_SDA") (class "Default")
      (node (ref "U7") (pin "1") (pinfunction "SDA_1") (pintype "bidirectional"))
      (node (ref "X-SOUTH") (pin "141") (pinfunction "141_141") (pintype "bidirectional"))
    )
    (net (code "238") (name "S_SDI") (class "Default")
      (node (ref "X-SOUTH") (pin "140") (pinfunction "140_140") (pintype "bidirectional"))
    )
    (net (code "239") (name "S_SDO") (class "Default")
      (node (ref "X-SOUTH") (pin "142") (pinfunction "142_142") (pintype "bidirectional"))
    )
    (net (code "240") (name "S_SPI_EN") (class "Default")
      (node (ref "X-SOUTH") (pin "136") (pinfunction "136_136") (pintype "bidirectional"))
    )
    (net (code "241") (name "S_SPI_V") (class "Default")
      (node (ref "X-SOUTH") (pin "134") (pinfunction "134_134") (pintype "bidirectional"))
    )
    (net (code "242") (name "S_VE") (class "Default")
      (node (ref "X-SOUTH") (pin "13") (pinfunction "13_13") (pintype "bidirectional"))
      (node (ref "X-SOUTH") (pin "19") (pinfunction "19_19") (pintype "bidirectional"))
      (node (ref "X-SOUTH") (pin "25") (pinfunction "25_25") (pintype "bidirectional"))
      (node (ref "X-SOUTH") (pin "31") (pinfunction "31_31") (pintype "bidirectional"))
      (node (ref "X-SOUTH") (pin "37") (pinfunction "37_37") (pintype "bidirectional"))
    )
    (net (code "243") (name "S_VE_CV") (class "Default")
      (node (ref "C11") (pin "1") (pinfunction "1_1") (pintype "passive"))
      (node (ref "R10") (pin "1") (pinfunction "1_1") (pintype "passive"))
      (node (ref "X-SOUTH") (pin "2") (pinfunction "2_2") (pintype "bidirectional"))
    )
    (net (code "244") (name "S_VE_OV") (class "Default")
      (node (ref "USE") (pin "7") (pinfunction "OUTB_7") (pintype "output"))
      (node (ref "X-SOUTH") (pin "1") (pinfunction "1_1") (pintype "bidirectional"))
    )
    (net (code "245") (name "S_VE_UV") (class "Default")
      (node (ref "USE") (pin "1") (pinfunction "OUTA_1") (pintype "output"))
      (node (ref "X-SOUTH") (pin "7") (pinfunction "7_7") (pintype "bidirectional"))
    )
    (net (code "246") (name "S_VS") (class "Default")
      (node (ref "C45") (pin "1") (pinfunction "1_1") (pintype "passive"))
      (node (ref "C46") (pin "1") (pinfunction "1_1") (pintype "passive"))
      (node (ref "C47") (pin "1") (pinfunction "1_1") (pintype "passive"))
      (node (ref "C48") (pin "1") (pinfunction "1_1") (pintype "passive"))
      (node (ref "C49") (pin "1") (pinfunction "1_1") (pintype "passive"))
      (node (ref "C72") (pin "1") (pinfunction "1_1") (pintype "passive"))
      (node (ref "C73") (pin "1") (pinfunction "1_1") (pintype "passive"))
      (node (ref "C74") (pin "1") (pinfunction "1_1") (pintype "passive"))
      (node (ref "C81") (pin "1") (pinfunction "1_1") (pintype "passive"))
      (node (ref "C82") (pin "1") (pinfunction "1_1") (pintype "passive"))
      (node (ref "C83") (pin "1") (pinfunction "1_1") (pintype "passive"))
      (node (ref "SENSOR") (pin "A30") (pinfunction "VDD_PIX_A30") (pintype "power_in"))
      (node (ref "SENSOR") (pin "D28") (pinfunction "VDD_PIX_D28") (pintype "power_in"))
      (node (ref "SENSOR") (pin "D30") (pinfunction "VDD_PIX_D30") (pintype "power_in"))
      (node (ref "SENSOR") (pin "G1") (pinfunction "VDD_PIX_G1") (pintype "power_in"))
      (node (ref "SENSOR") (pin "H28") (pinfunction "VDD_PIX_H28") (pintype "power_in"))
      (node (ref "TP6") (pin "TP") (pinfunction "TP_TP") (pintype "input"))
      (node (ref "X-SOUTH") (pin "49") (pinfunction "49_49") (pintype "bidirectional"))
      (node (ref "X-SOUTH") (pin "55") (pinfunction "55_55") (pintype "bidirectional"))
      (node (ref "X-SOUTH") (pin "61") (pinfunction "61_61") (pintype "bidirectional"))
      (node (ref "X-SOUTH") (pin "67") (pinfunction "67_67") (pintype "bidirectional"))
      (node (ref "X-SOUTH") (pin "73") (pinfunction "73_73") (pintype "bidirectional"))
      (node (ref "X-SOUTH") (pin "79") (pinfunction "79_79") (pintype "bidirectional"))
      (node (ref "X-SOUTH") (pin "85") (pinfunction "85_85") (pintype "bidirectional"))
      (node (ref "X-SOUTH") (pin "91") (pinfunction "91_91") (pintype "bidirectional"))
      (node (ref "X-SOUTH") (pin "97") (pinfunction "97_97") (pintype "bidirectional"))
    )
    (net (code "247") (name "S_VS_CV") (class "Default")
      (node (ref "C12") (pin "1") (pinfunction "1_1") (pintype "passive"))
      (node (ref "R13") (pin "1") (pinfunction "1_1") (pintype "passive"))
      (node (ref "X-SOUTH") (pin "4") (pinfunction "4_4") (pintype "bidirectional"))
    )
    (net (code "248") (name "S_VS_OV") (class "Default")
      (node (ref "USS") (pin "7") (pinfunction "OUTB_7") (pintype "output"))
      (node (ref "X-SOUTH") (pin "3") (pinfunction "3_3") (pintype "bidirectional"))
    )
    (net (code "249") (name "S_VS_UV") (class "Default")
      (node (ref "USS") (pin "1") (pinfunction "OUTA_1") (pintype "output"))
      (node (ref "X-SOUTH") (pin "9") (pinfunction "9_9") (pintype "bidirectional"))
    )
    (net (code "250") (name "S_VW") (class "Default")
      (node (ref "C90") (pin "1") (pinfunction "1_1") (pintype "passive"))
      (node (ref "U3") (pin "1") (pinfunction "BIAS_1") (pintype "power_in"))
      (node (ref "U3") (pin "3") (pinfunction "IN_3") (pintype "power_in"))
      (node (ref "X-SOUTH") (pin "109") (pinfunction "109_109") (pintype "bidirectional"))
      (node (ref "X-SOUTH") (pin "115") (pinfunction "115_115") (pintype "bidirectional"))
      (node (ref "X-SOUTH") (pin "121") (pinfunction "121_121") (pintype "bidirectional"))
      (node (ref "X-SOUTH") (pin "127") (pinfunction "127_127") (pintype "bidirectional"))
      (node (ref "X-SOUTH") (pin "133") (pinfunction "133_133") (pintype "bidirectional"))
    )
    (net (code "251") (name "S_VW_CV") (class "Default")
      (node (ref "C13") (pin "1") (pinfunction "1_1") (pintype "passive"))
      (node (ref "R16") (pin "1") (pinfunction "1_1") (pintype "passive"))
      (node (ref "X-SOUTH") (pin "6") (pinfunction "6_6") (pintype "bidirectional"))
    )
    (net (code "252") (name "S_VW_OV") (class "Default")
      (node (ref "USW") (pin "7") (pinfunction "OUTB_7") (pintype "output"))
      (node (ref "X-SOUTH") (pin "5") (pinfunction "5_5") (pintype "bidirectional"))
    )
    (net (code "253") (name "S_VW_UV") (class "Default")
      (node (ref "USW") (pin "1") (pinfunction "OUTA_1") (pintype "output"))
      (node (ref "X-SOUTH") (pin "11") (pinfunction "11_11") (pintype "bidirectional"))
    )
    (net (code "254") (name "TDIG1") (class "Default")
      (node (ref "SENSOR") (pin "G27") (pinfunction "TDIG1_G27") (pintype "output"))
      (node (ref "U5") (pin "9") (pinfunction "B4_9") (pintype "bidirectional"))
    )
    (net (code "255") (name "TDIG2") (class "Default")
      (node (ref "SENSOR") (pin "G26") (pinfunction "TDIG2_G26") (pintype "output"))
      (node (ref "U6") (pin "11") (pinfunction "B2_11") (pintype "bidirectional"))
    )
    (net (code "256") (name "T_EXP1") (class "Default")
      (node (ref "SENSOR") (pin "H30") (pinfunction "T_EXP1_H30") (pintype "input"))
      (node (ref "U5") (pin "12") (pinfunction "B1_12") (pintype "bidirectional"))
    )
    (net (code "257") (name "T_EXP2") (class "Default")
      (node (ref "SENSOR") (pin "E29") (pinfunction "T_EXP2_E29") (pintype "input"))
      (node (ref "U6") (pin "10") (pinfunction "B3_10") (pintype "bidirectional"))
    )
    (net (code "258") (name "VRAMP1") (class "Default")
      (node (ref "C16") (pin "1") (pinfunction "1_1") (pintype "passive"))
      (node (ref "R23") (pin "1") (pinfunction "1_1") (pintype "passive"))
      (node (ref "SENSOR") (pin "G29") (pinfunction "VRAMP1_G29") (pintype "bidirectional"))
    )
    (net (code "259") (name "VRAMP2") (class "Default")
      (node (ref "C17") (pin "1") (pinfunction "1_1") (pintype "passive"))
      (node (ref "R23") (pin "2") (pinfunction "2_2") (pintype "passive"))
      (node (ref "SENSOR") (pin "F29") (pinfunction "VRAMP2_F29") (pintype "bidirectional"))
    )
    (net (code "260") (name "VTREF") (class "Default")
      (node (ref "C65") (pin "1") (pinfunction "1_1") (pintype "passive"))
      (node (ref "C91") (pin "2") (pinfunction "2_2") (pintype "passive"))
      (node (ref "R21") (pin "2") (pinfunction "2_2") (pintype "passive"))
      (node (ref "R24") (pin "1") (pinfunction "1_1") (pintype "passive"))
      (node (ref "SENSOR") (pin "B2") (pinfunction "VTREF_B2") (pintype "bidirectional"))
      (node (ref "U3") (pin "4") (pinfunction "OUT_4") (pintype "power_in"))
    )
    (net (code "261") (name "VTSIG") (class "Default")
      (node (ref "C66") (pin "1") (pinfunction "1_1") (pintype "passive"))
      (node (ref "R24") (pin "2") (pinfunction "2_2") (pintype "passive"))
      (node (ref "SENSOR") (pin "C2") (pinfunction "VTSIG_C2") (pintype "bidirectional"))
    )
    (net (code "262") (name "unconnected-(U1-NC-Pad2)") (class "Default")
      (node (ref "U1") (pin "2") (pinfunction "NC_2") (pintype "no_connect"))
    )
    (net (code "263") (name "unconnected-(U1-NC-Pad4)") (class "Default")
      (node (ref "U1") (pin "4") (pinfunction "NC_4") (pintype "no_connect"))
    )
    (net (code "264") (name "unconnected-(U1-NC-Pad5)") (class "Default")
      (node (ref "U1") (pin "5") (pinfunction "NC_5") (pintype "no_connect"))
    )
    (net (code "265") (name "unconnected-(U2-NC-Pad2)") (class "Default")
      (node (ref "U2") (pin "2") (pinfunction "NC_2") (pintype "no_connect"))
    )
    (net (code "266") (name "unconnected-(U2-NC-Pad4)") (class "Default")
      (node (ref "U2") (pin "4") (pinfunction "NC_4") (pintype "no_connect"))
    )
    (net (code "267") (name "unconnected-(U2-NC-Pad5)") (class "Default")
      (node (ref "U2") (pin "5") (pinfunction "NC_5") (pintype "no_connect"))
    )
    (net (code "268") (name "unconnected-(U7-OS-Pad3)") (class "Default")
      (node (ref "U7") (pin "3") (pinfunction "OS_3") (pintype "output"))
    )
    (net (code "269") (name "unconnected-(X-NORTH-PadM1)") (class "Default")
      (node (ref "X-NORTH") (pin "M1") (pinfunction "M1_M1") (pintype "bidirectional"))
    )
    (net (code "270") (name "unconnected-(X-NORTH-PadM2)") (class "Default")
      (node (ref "X-NORTH") (pin "M2") (pinfunction "M2_M2") (pintype "bidirectional"))
    )
    (net (code "271") (name "unconnected-(X-SOUTH-PadM1)") (class "Default")
      (node (ref "X-SOUTH") (pin "M1") (pinfunction "M1_M1") (pintype "bidirectional"))
    )
    (net (code "272") (name "unconnected-(X-SOUTH-PadM2)") (class "Default")
      (node (ref "X-SOUTH") (pin "M2") (pinfunction "M2_M2") (pintype "bidirectional"))
    )
  )
)
